# lcdTestBoard.net
KiCad netlist of a schematic drawn in EAGLE
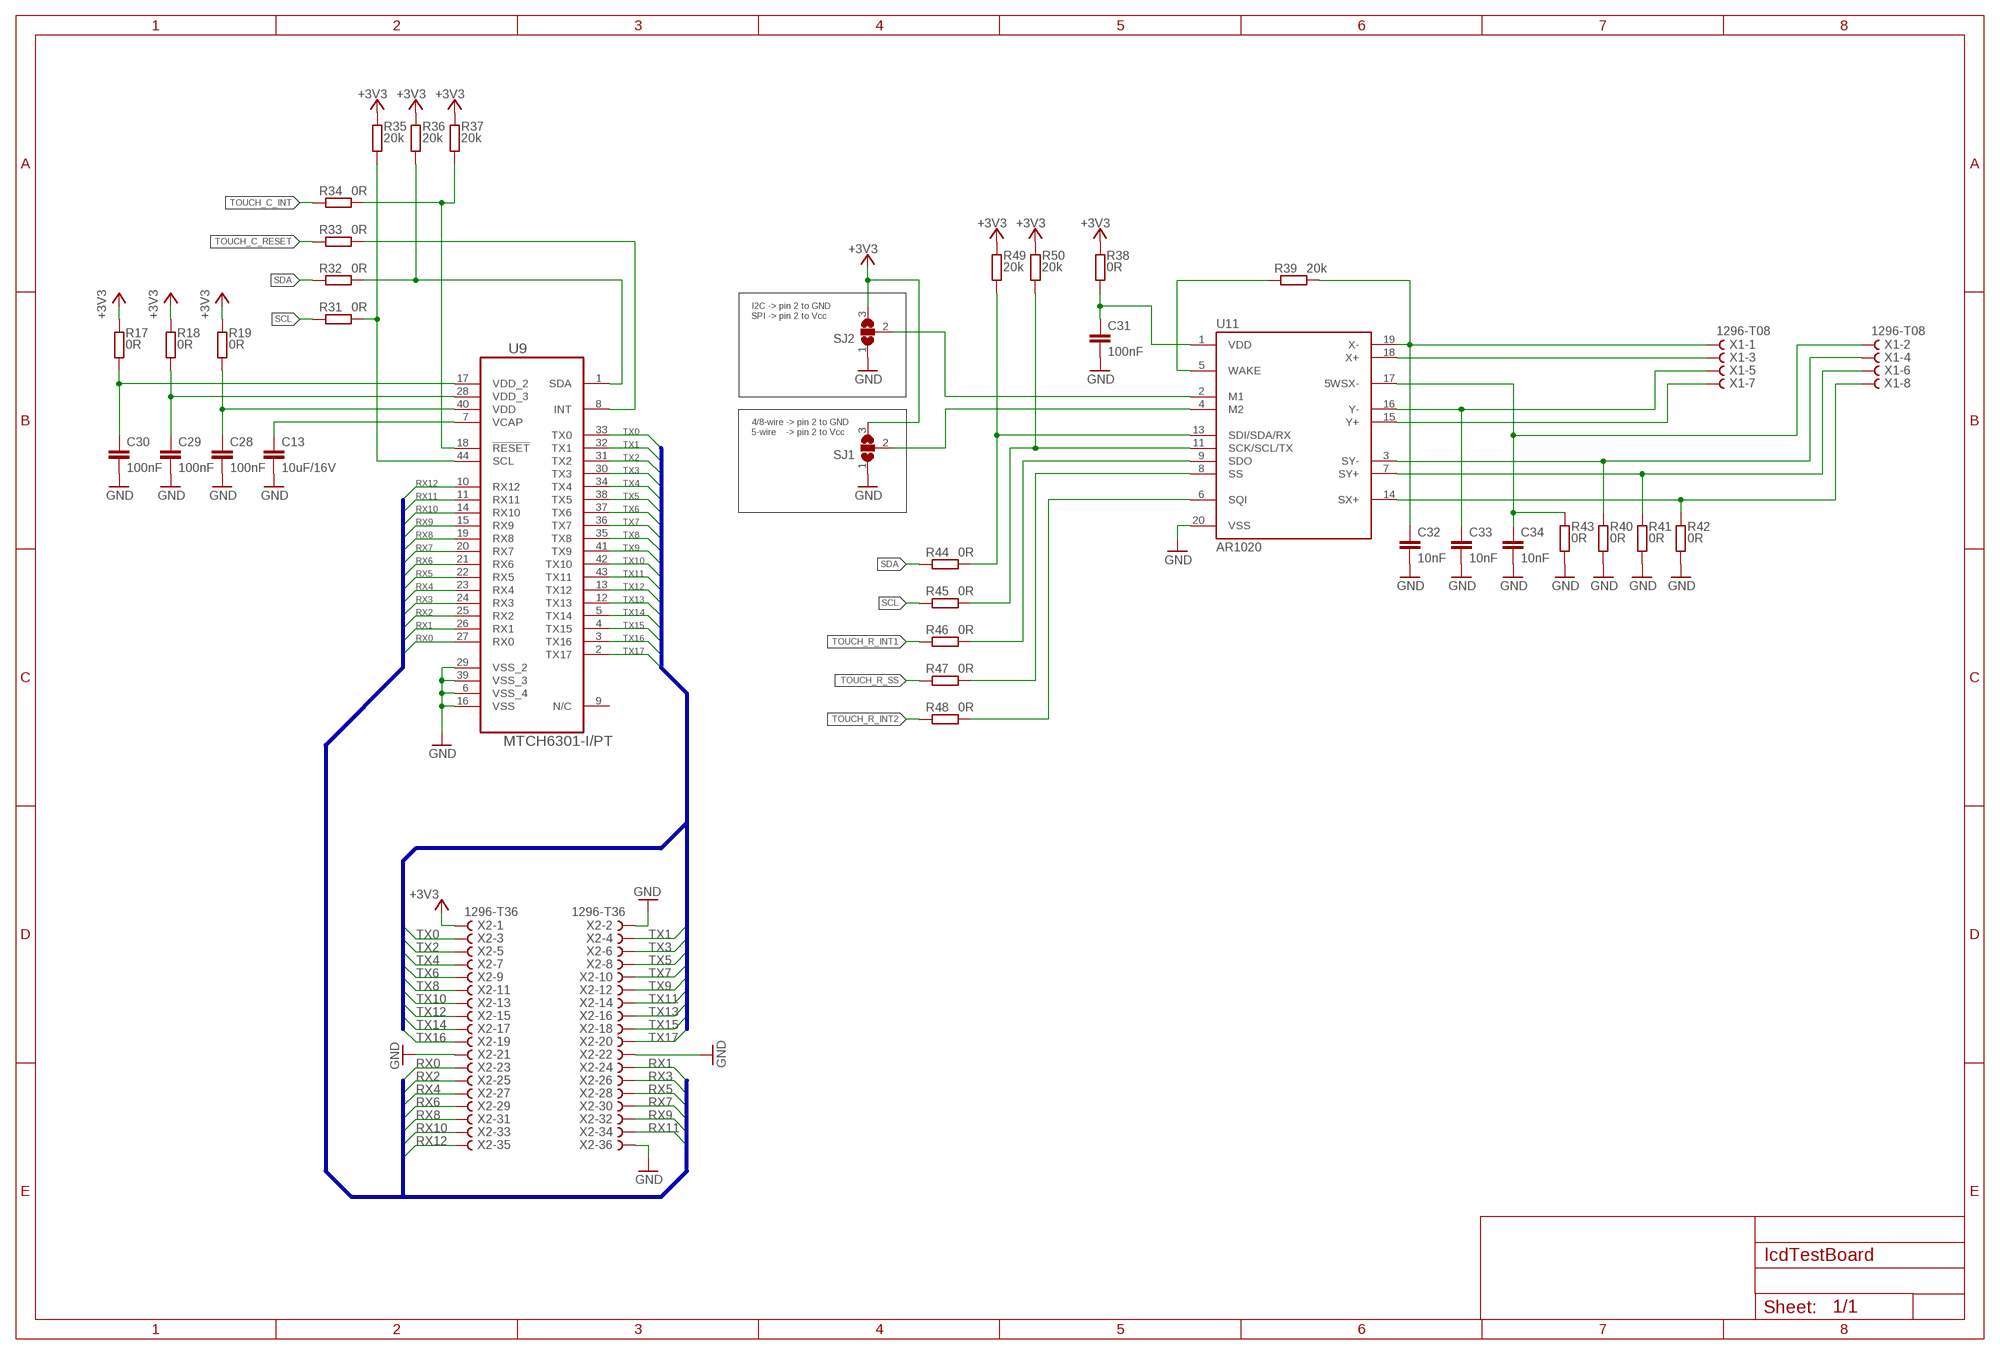
[diagram p0: schematic, sheet 1, part 1 of 3]
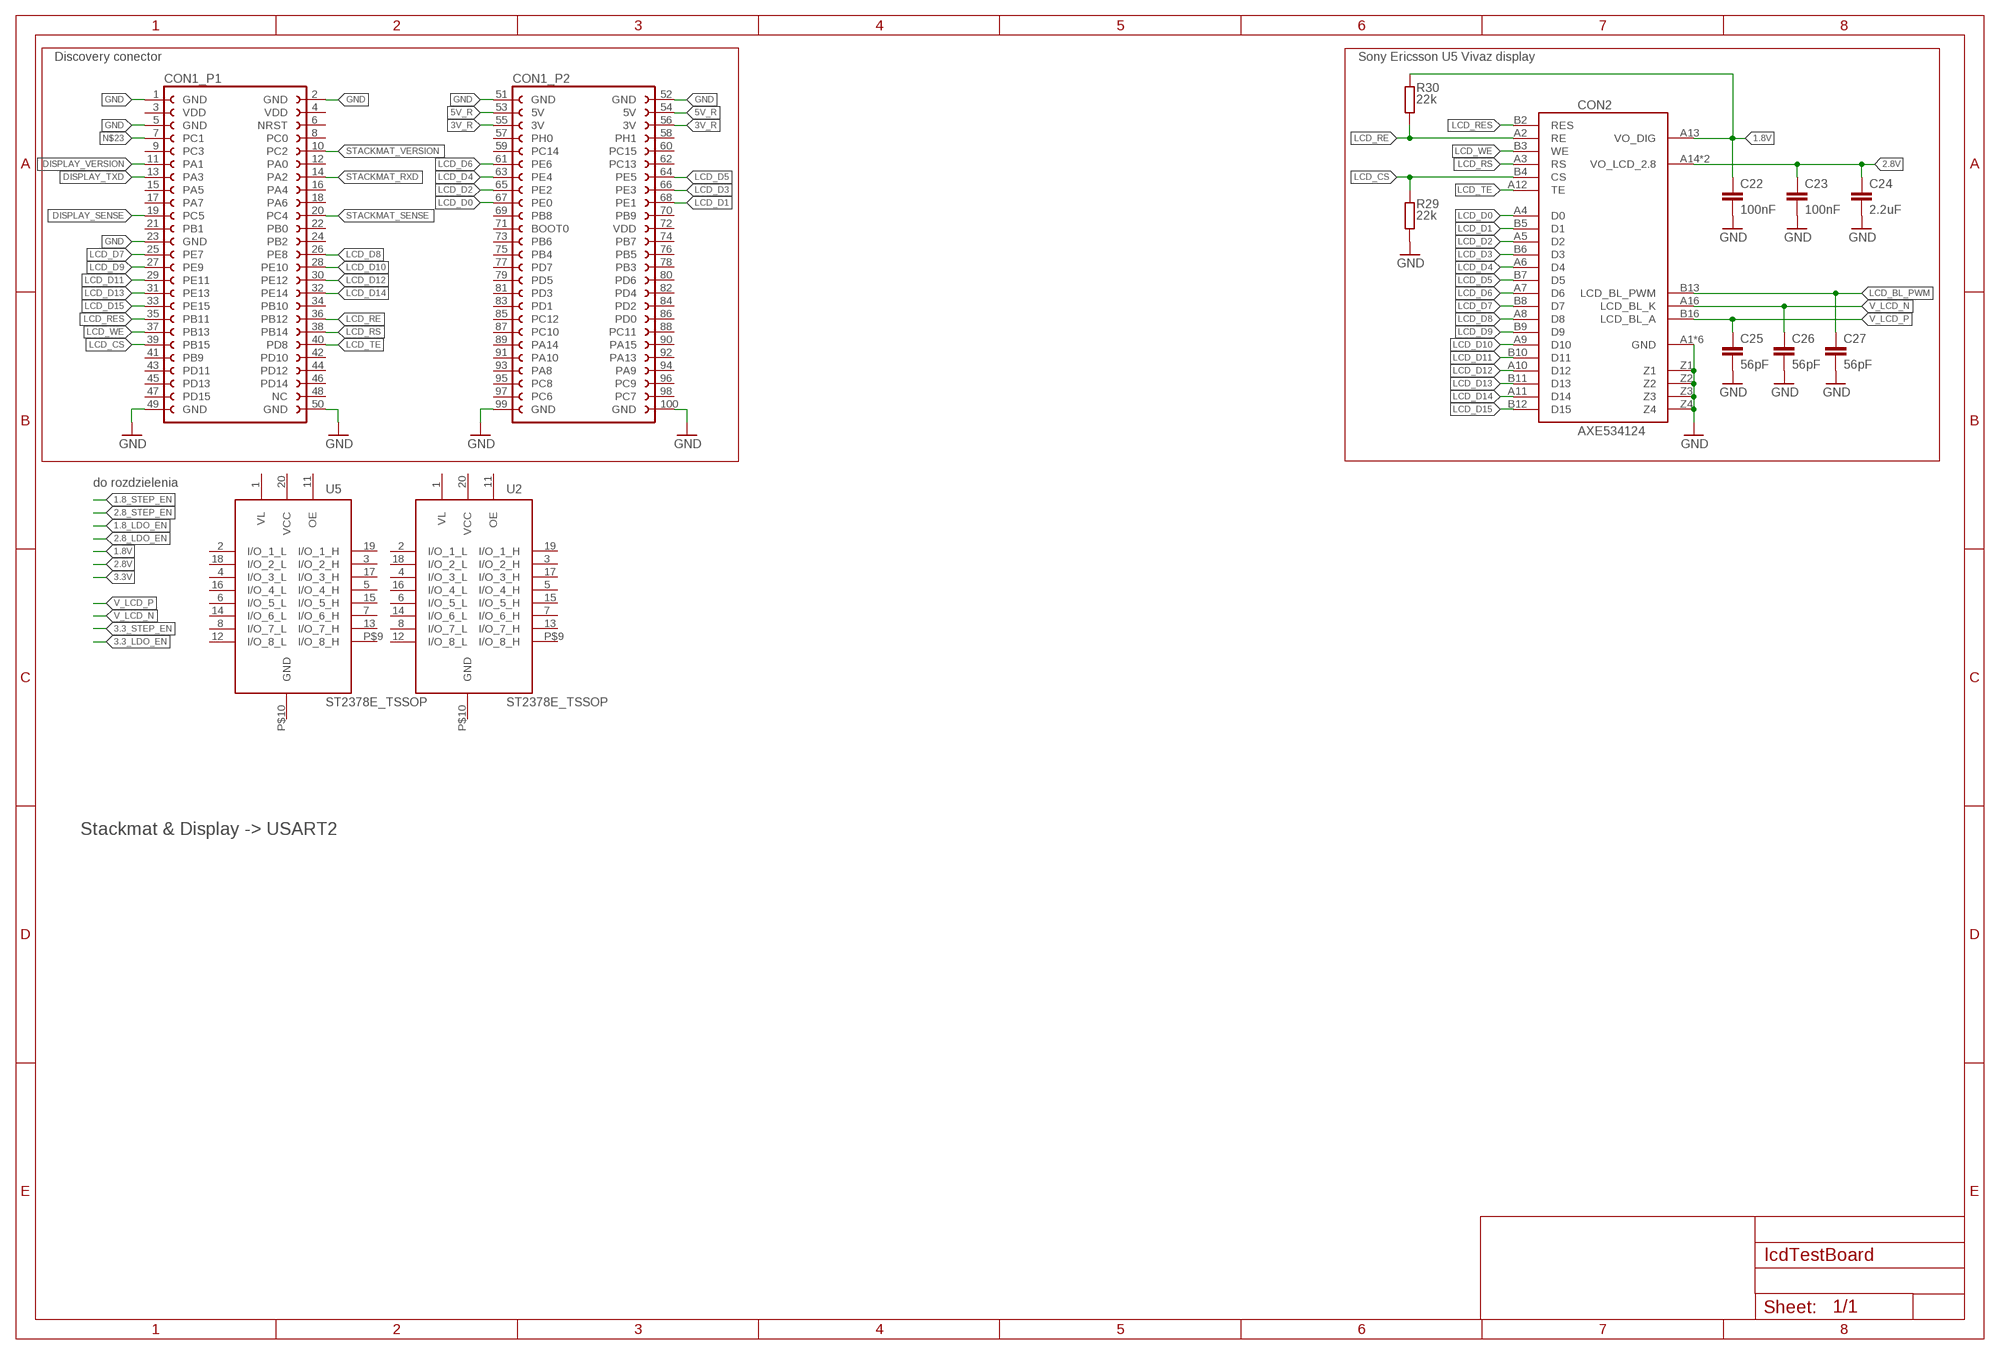
[diagram p1: schematic, sheet 1, part 2 of 3]
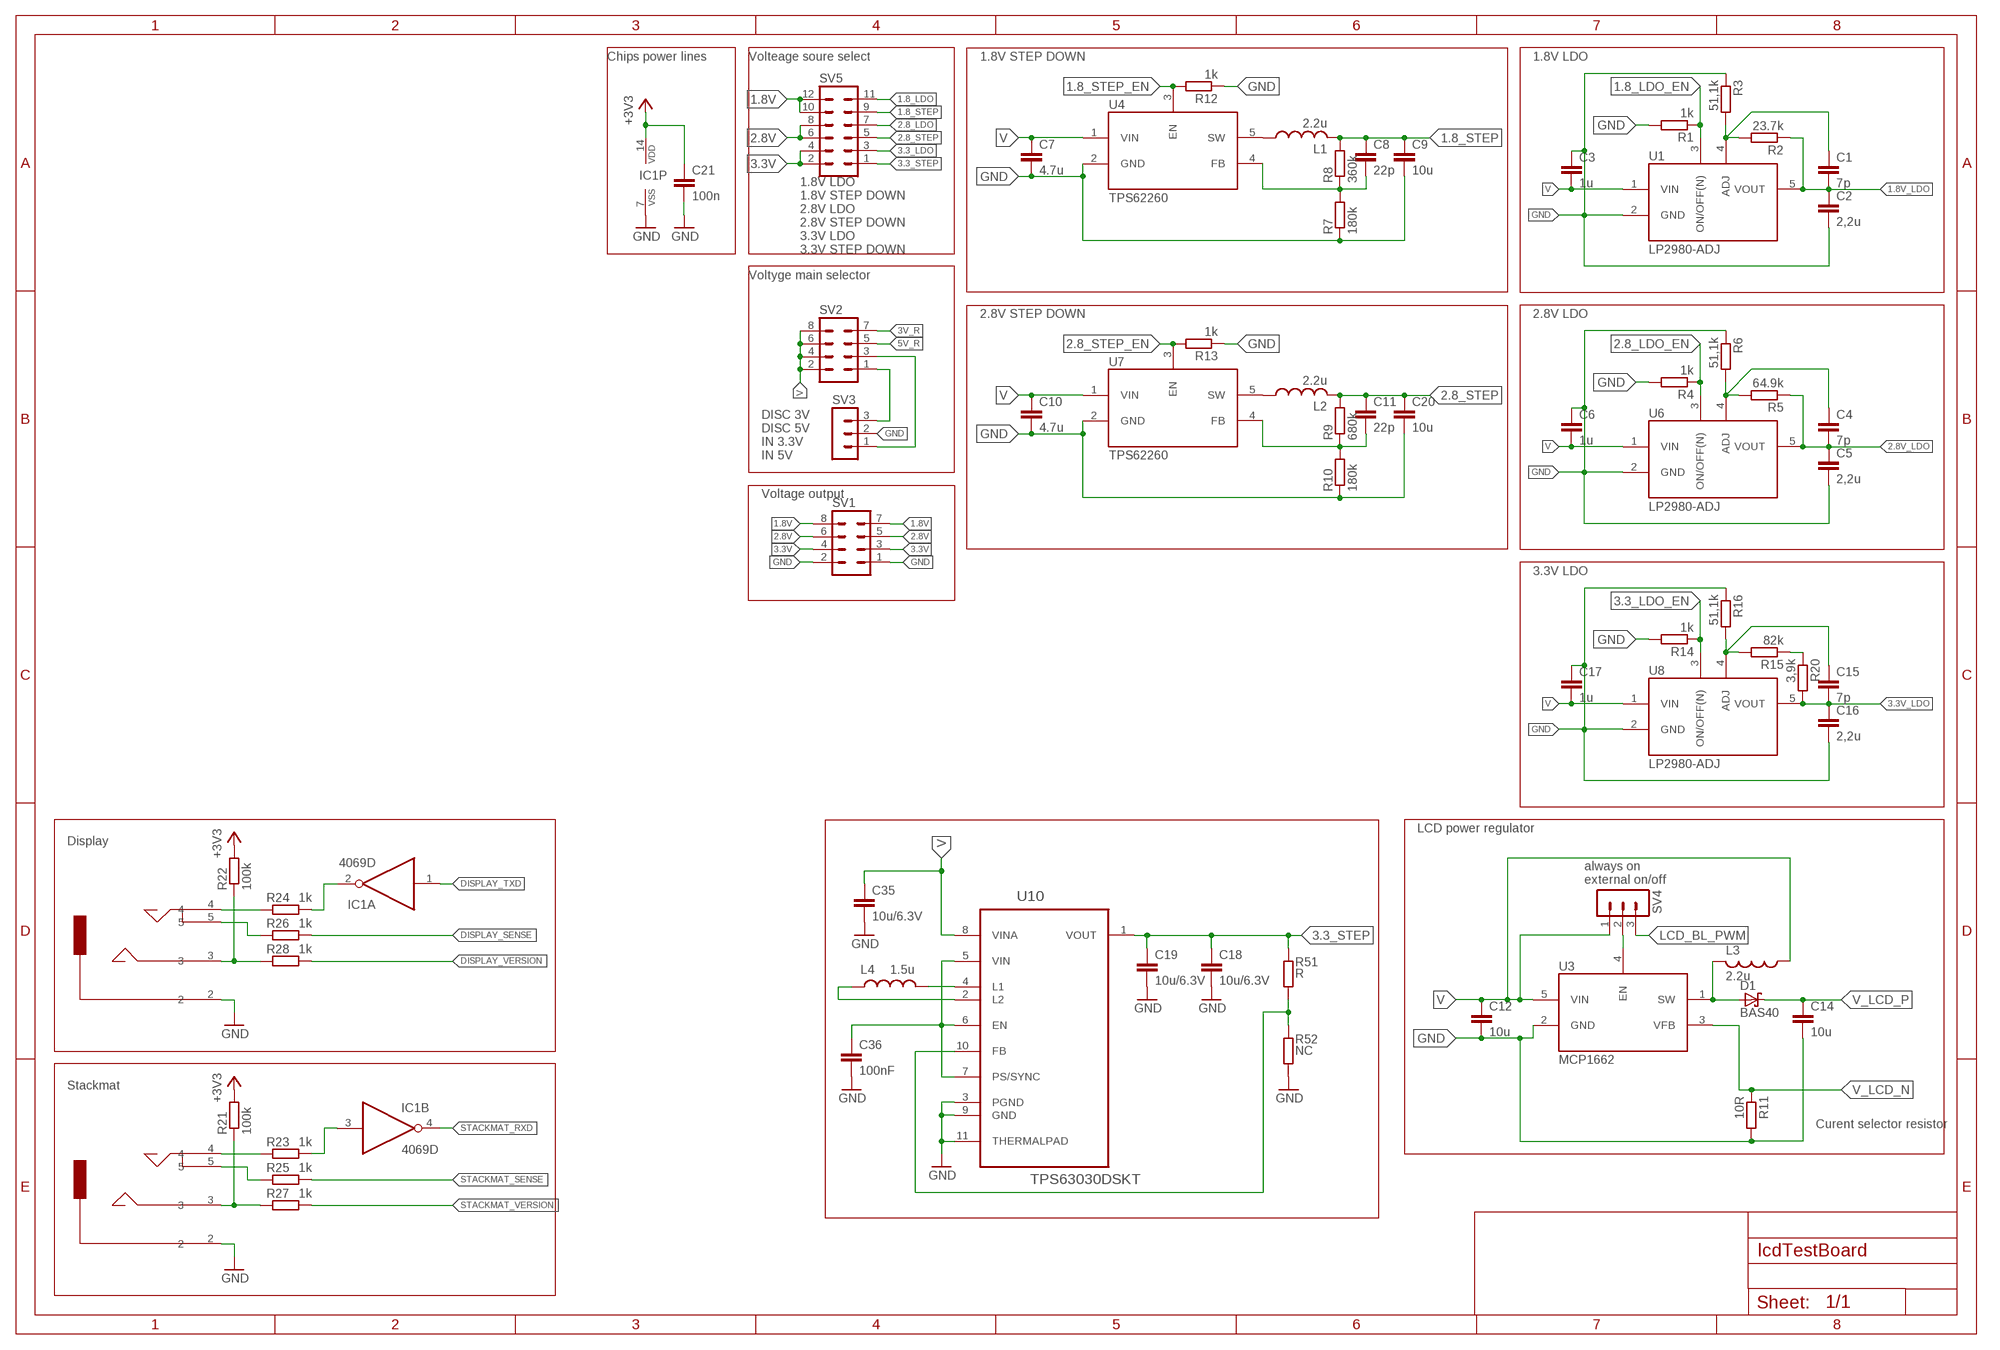
[diagram p2: schematic, sheet 1, part 3 of 3]

(export (version "E")
  (design (tool "Eeschema 10.0.6"))
  (components
    (comp (ref "C1")
      (value "7p")
      (footprint "eagle-import:C0603")
      (libsource (lib "eagle-import") (part "C-EUC0603"))
    )
    (comp (ref "C2")
      (value "2,2u")
      (footprint "eagle-import:C0603")
      (libsource (lib "eagle-import") (part "C-EUC0603"))
    )
    (comp (ref "C3")
      (value "1u")
      (footprint "eagle-import:C0603")
      (libsource (lib "eagle-import") (part "C-EUC0603"))
    )
    (comp (ref "C4")
      (value "7p")
      (footprint "eagle-import:C0603")
      (libsource (lib "eagle-import") (part "C-EUC0603"))
    )
    (comp (ref "C5")
      (value "2,2u")
      (footprint "eagle-import:C0603")
      (libsource (lib "eagle-import") (part "C-EUC0603"))
    )
    (comp (ref "C6")
      (value "1u")
      (footprint "eagle-import:C0603")
      (libsource (lib "eagle-import") (part "C-EUC0603"))
    )
    (comp (ref "C7")
      (value "4.7u")
      (footprint "eagle-import:C0603")
      (libsource (lib "eagle-import") (part "C-EUC0603"))
    )
    (comp (ref "C8")
      (value "22p")
      (footprint "eagle-import:C0603")
      (libsource (lib "eagle-import") (part "C-EUC0603"))
    )
    (comp (ref "C9")
      (value "10u")
      (footprint "eagle-import:C1206")
      (libsource (lib "eagle-import") (part "C-EUC1206"))
    )
    (comp (ref "C10")
      (value "4.7u")
      (footprint "eagle-import:C0603")
      (libsource (lib "eagle-import") (part "C-EUC0603"))
    )
    (comp (ref "C11")
      (value "22p")
      (footprint "eagle-import:C0603")
      (libsource (lib "eagle-import") (part "C-EUC0603"))
    )
    (comp (ref "C12")
      (value "10u")
      (footprint "eagle-import:C1206")
      (libsource (lib "eagle-import") (part "C-EUC1206"))
    )
    (comp (ref "C13")
      (value "10uF/16V")
      (footprint "eagle-import:C1206K")
      (libsource (lib "eagle-import") (part "C-EUC1206K"))
    )
    (comp (ref "C14")
      (value "10u")
      (footprint "eagle-import:C1206")
      (libsource (lib "eagle-import") (part "C-EUC1206"))
    )
    (comp (ref "C15")
      (value "7p")
      (footprint "eagle-import:C0603")
      (libsource (lib "eagle-import") (part "C-EUC0603"))
    )
    (comp (ref "C16")
      (value "2,2u")
      (footprint "eagle-import:C0603")
      (libsource (lib "eagle-import") (part "C-EUC0603"))
    )
    (comp (ref "C17")
      (value "1u")
      (footprint "eagle-import:C0603")
      (libsource (lib "eagle-import") (part "C-EUC0603"))
    )
    (comp (ref "C18")
      (value "10u/6.3V")
      (footprint "eagle-import:C1206")
      (libsource (lib "eagle-import") (part "C-EUC1206"))
    )
    (comp (ref "C19")
      (value "10u/6.3V")
      (footprint "eagle-import:C1206")
      (libsource (lib "eagle-import") (part "C-EUC1206"))
    )
    (comp (ref "C20")
      (value "10u")
      (footprint "eagle-import:C1206")
      (libsource (lib "eagle-import") (part "C-EUC1206"))
    )
    (comp (ref "C21")
      (value "100n")
      (footprint "eagle-import:C0603K")
      (libsource (lib "eagle-import") (part "C-EUC0603K"))
    )
    (comp (ref "C22")
      (value "100nF")
      (footprint "eagle-import:C0603K")
      (libsource (lib "eagle-import") (part "C-EUC0603K"))
    )
    (comp (ref "C23")
      (value "100nF")
      (footprint "eagle-import:C0603K")
      (libsource (lib "eagle-import") (part "C-EUC0603K"))
    )
    (comp (ref "C24")
      (value "2.2uF")
      (footprint "eagle-import:C0603K")
      (libsource (lib "eagle-import") (part "C-EUC0603K"))
    )
    (comp (ref "C25")
      (value "56pF")
      (footprint "eagle-import:C0603K")
      (libsource (lib "eagle-import") (part "C-EUC0603K"))
    )
    (comp (ref "C26")
      (value "56pF")
      (footprint "eagle-import:C0603K")
      (libsource (lib "eagle-import") (part "C-EUC0603K"))
    )
    (comp (ref "C27")
      (value "56pF")
      (footprint "eagle-import:C0603K")
      (libsource (lib "eagle-import") (part "C-EUC0603K"))
    )
    (comp (ref "C28")
      (value "100nF")
      (footprint "eagle-import:C0603K")
      (libsource (lib "eagle-import") (part "C-EUC0603K"))
    )
    (comp (ref "C29")
      (value "100nF")
      (footprint "eagle-import:C0603K")
      (libsource (lib "eagle-import") (part "C-EUC0603K"))
    )
    (comp (ref "C30")
      (value "100nF")
      (footprint "eagle-import:C0603K")
      (libsource (lib "eagle-import") (part "C-EUC0603K"))
    )
    (comp (ref "C31")
      (value "100nF")
      (footprint "eagle-import:C0603K")
      (libsource (lib "eagle-import") (part "C-EUC0603K"))
    )
    (comp (ref "C32")
      (value "10nF")
      (footprint "eagle-import:C0603K")
      (libsource (lib "eagle-import") (part "C-EUC0603K"))
    )
    (comp (ref "C33")
      (value "10nF")
      (footprint "eagle-import:C0603K")
      (libsource (lib "eagle-import") (part "C-EUC0603K"))
    )
    (comp (ref "C34")
      (value "10nF")
      (footprint "eagle-import:C0603K")
      (libsource (lib "eagle-import") (part "C-EUC0603K"))
    )
    (comp (ref "C35")
      (value "10u/6.3V")
      (footprint "eagle-import:C1206")
      (libsource (lib "eagle-import") (part "C-EUC1206"))
    )
    (comp (ref "C36")
      (value "100nF")
      (footprint "eagle-import:C1206")
      (libsource (lib "eagle-import") (part "C-EUC1206"))
    )
    (comp (ref "CON1")
      (value "STM32F4DISCOVERY-CONNECTOR")
      (footprint "eagle-import:STM32F4DISCOVERY_CONNECTOR")
      (libsource (lib "eagle-import") (part "STM32F4DISCOVERY-CONNECTOR"))
    )
    (comp (ref "CON2")
      (value "AXE534124")
      (footprint "eagle-import:SOCKET")
      (libsource (lib "eagle-import") (part "AXE534124"))
    )
    (comp (ref "D1")
      (value "BAS40")
      (footprint "eagle-import:SOT23")
      (libsource (lib "eagle-import") (part "BAS40"))
    )
    (comp (ref "IC1")
      (value "4069D")
      (footprint "eagle-import:SO14")
      (libsource (lib "eagle-import") (part "4069D"))
    )
    (comp (ref "L1")
      (value "2.2u")
      (footprint "eagle-import:L2012C")
      (libsource (lib "eagle-import") (part "L-USL2012C"))
    )
    (comp (ref "L2")
      (value "2.2u")
      (footprint "eagle-import:L2012C")
      (libsource (lib "eagle-import") (part "L-USL2012C"))
    )
    (comp (ref "L3")
      (value "2.2u")
      (footprint "eagle-import:L2012C")
      (libsource (lib "eagle-import") (part "L-USL2012C"))
    )
    (comp (ref "L4")
      (value "1.5u")
      (footprint "eagle-import:L2012C")
      (libsource (lib "eagle-import") (part "L-USL2012C"))
    )
    (comp (ref "R1")
      (value "1k")
      (footprint "eagle-import:R0603")
      (libsource (lib "eagle-import") (part "R-EU_R0603"))
    )
    (comp (ref "R2")
      (value "23.7k")
      (footprint "eagle-import:R0603")
      (libsource (lib "eagle-import") (part "R-EU_R0603"))
    )
    (comp (ref "R3")
      (value "51,1k")
      (footprint "eagle-import:R0603")
      (libsource (lib "eagle-import") (part "R-EU_R0603"))
    )
    (comp (ref "R4")
      (value "1k")
      (footprint "eagle-import:R0603")
      (libsource (lib "eagle-import") (part "R-EU_R0603"))
    )
    (comp (ref "R5")
      (value "64.9k")
      (footprint "eagle-import:R0603")
      (libsource (lib "eagle-import") (part "R-EU_R0603"))
    )
    (comp (ref "R6")
      (value "51,1k")
      (footprint "eagle-import:R0603")
      (libsource (lib "eagle-import") (part "R-EU_R0603"))
    )
    (comp (ref "R7")
      (value "180k")
      (footprint "eagle-import:R0603")
      (libsource (lib "eagle-import") (part "R-EU_R0603"))
    )
    (comp (ref "R8")
      (value "360k")
      (footprint "eagle-import:R0603")
      (libsource (lib "eagle-import") (part "R-EU_R0603"))
    )
    (comp (ref "R9")
      (value "680k")
      (footprint "eagle-import:R0603")
      (libsource (lib "eagle-import") (part "R-EU_R0603"))
    )
    (comp (ref "R10")
      (value "180k")
      (footprint "eagle-import:R0603")
      (libsource (lib "eagle-import") (part "R-EU_R0603"))
    )
    (comp (ref "R11")
      (value "10R")
      (footprint "eagle-import:R0603")
      (libsource (lib "eagle-import") (part "R-EU_R0603"))
    )
    (comp (ref "R12")
      (value "1k")
      (footprint "eagle-import:R0603")
      (libsource (lib "eagle-import") (part "R-EU_R0603"))
    )
    (comp (ref "R13")
      (value "1k")
      (footprint "eagle-import:R0603")
      (libsource (lib "eagle-import") (part "R-EU_R0603"))
    )
    (comp (ref "R14")
      (value "1k")
      (footprint "eagle-import:R0603")
      (libsource (lib "eagle-import") (part "R-EU_R0603"))
    )
    (comp (ref "R15")
      (value "82k")
      (footprint "eagle-import:R0603")
      (libsource (lib "eagle-import") (part "R-EU_R0603"))
    )
    (comp (ref "R16")
      (value "51,1k")
      (footprint "eagle-import:R0603")
      (libsource (lib "eagle-import") (part "R-EU_R0603"))
    )
    (comp (ref "R17")
      (value "0R")
      (footprint "eagle-import:R0603")
      (libsource (lib "eagle-import") (part "R-EU_R0603"))
    )
    (comp (ref "R18")
      (value "0R")
      (footprint "eagle-import:R0603")
      (libsource (lib "eagle-import") (part "R-EU_R0603"))
    )
    (comp (ref "R19")
      (value "0R")
      (footprint "eagle-import:R0603")
      (libsource (lib "eagle-import") (part "R-EU_R0603"))
    )
    (comp (ref "R20")
      (value "3,9k")
      (footprint "eagle-import:R0603")
      (libsource (lib "eagle-import") (part "R-EU_R0603"))
    )
    (comp (ref "R21")
      (value "100k")
      (footprint "eagle-import:R0603")
      (libsource (lib "eagle-import") (part "R-EU_R0603"))
    )
    (comp (ref "R22")
      (value "100k")
      (footprint "eagle-import:R0603")
      (libsource (lib "eagle-import") (part "R-EU_R0603"))
    )
    (comp (ref "R23")
      (value "1k")
      (footprint "eagle-import:R0603")
      (libsource (lib "eagle-import") (part "R-EU_R0603"))
    )
    (comp (ref "R24")
      (value "1k")
      (footprint "eagle-import:R0603")
      (libsource (lib "eagle-import") (part "R-EU_R0603"))
    )
    (comp (ref "R25")
      (value "1k")
      (footprint "eagle-import:R0603")
      (libsource (lib "eagle-import") (part "R-EU_R0603"))
    )
    (comp (ref "R26")
      (value "1k")
      (footprint "eagle-import:R0603")
      (libsource (lib "eagle-import") (part "R-EU_R0603"))
    )
    (comp (ref "R27")
      (value "1k")
      (footprint "eagle-import:R0603")
      (libsource (lib "eagle-import") (part "R-EU_R0603"))
    )
    (comp (ref "R28")
      (value "1k")
      (footprint "eagle-import:R0603")
      (libsource (lib "eagle-import") (part "R-EU_R0603"))
    )
    (comp (ref "R29")
      (value "22k")
      (footprint "eagle-import:R0603")
      (libsource (lib "eagle-import") (part "R-EU_R0603"))
    )
    (comp (ref "R30")
      (value "22k")
      (footprint "eagle-import:R0603")
      (libsource (lib "eagle-import") (part "R-EU_R0603"))
    )
    (comp (ref "R31")
      (value "0R")
      (footprint "eagle-import:R0603")
      (libsource (lib "eagle-import") (part "R-EU_R0603"))
    )
    (comp (ref "R32")
      (value "0R")
      (footprint "eagle-import:R0603")
      (libsource (lib "eagle-import") (part "R-EU_R0603"))
    )
    (comp (ref "R33")
      (value "0R")
      (footprint "eagle-import:R0603")
      (libsource (lib "eagle-import") (part "R-EU_R0603"))
    )
    (comp (ref "R34")
      (value "0R")
      (footprint "eagle-import:R0603")
      (libsource (lib "eagle-import") (part "R-EU_R0603"))
    )
    (comp (ref "R35")
      (value "20k")
      (footprint "eagle-import:R0603")
      (libsource (lib "eagle-import") (part "R-EU_R0603"))
    )
    (comp (ref "R36")
      (value "20k")
      (footprint "eagle-import:R0603")
      (libsource (lib "eagle-import") (part "R-EU_R0603"))
    )
    (comp (ref "R37")
      (value "20k")
      (footprint "eagle-import:R0603")
      (libsource (lib "eagle-import") (part "R-EU_R0603"))
    )
    (comp (ref "R38")
      (value "0R")
      (footprint "eagle-import:R0603")
      (libsource (lib "eagle-import") (part "R-EU_R0603"))
    )
    (comp (ref "R39")
      (value "20k")
      (footprint "eagle-import:R0603")
      (libsource (lib "eagle-import") (part "R-EU_R0603"))
    )
    (comp (ref "R40")
      (value "0R")
      (footprint "eagle-import:R0603")
      (libsource (lib "eagle-import") (part "R-EU_R0603"))
    )
    (comp (ref "R41")
      (value "0R")
      (footprint "eagle-import:R0603")
      (libsource (lib "eagle-import") (part "R-EU_R0603"))
    )
    (comp (ref "R42")
      (value "0R")
      (footprint "eagle-import:R0603")
      (libsource (lib "eagle-import") (part "R-EU_R0603"))
    )
    (comp (ref "R43")
      (value "0R")
      (footprint "eagle-import:R0603")
      (libsource (lib "eagle-import") (part "R-EU_R0603"))
    )
    (comp (ref "R44")
      (value "0R")
      (footprint "eagle-import:R0603")
      (libsource (lib "eagle-import") (part "R-EU_R0603"))
    )
    (comp (ref "R45")
      (value "0R")
      (footprint "eagle-import:R0603")
      (libsource (lib "eagle-import") (part "R-EU_R0603"))
    )
    (comp (ref "R46")
      (value "0R")
      (footprint "eagle-import:R0603")
      (libsource (lib "eagle-import") (part "R-EU_R0603"))
    )
    (comp (ref "R47")
      (value "0R")
      (footprint "eagle-import:R0603")
      (libsource (lib "eagle-import") (part "R-EU_R0603"))
    )
    (comp (ref "R48")
      (value "0R")
      (footprint "eagle-import:R0603")
      (libsource (lib "eagle-import") (part "R-EU_R0603"))
    )
    (comp (ref "R49")
      (value "20k")
      (footprint "eagle-import:R0603")
      (libsource (lib "eagle-import") (part "R-EU_R0603"))
    )
    (comp (ref "R50")
      (value "20k")
      (footprint "eagle-import:R0603")
      (libsource (lib "eagle-import") (part "R-EU_R0603"))
    )
    (comp (ref "R51")
      (value "R")
      (footprint "eagle-import:R0603")
      (libsource (lib "eagle-import") (part "R-EU_R0603"))
    )
    (comp (ref "R52")
      (value "NC")
      (footprint "eagle-import:R0603")
      (libsource (lib "eagle-import") (part "R-EU_R0603"))
    )
    (comp (ref "SJ1")
      (value "SJ2W")
      (footprint "eagle-import:SJ_2")
      (libsource (lib "eagle-import") (part "SJ2W"))
    )
    (comp (ref "SJ2")
      (value "SJ2W")
      (footprint "eagle-import:SJ_2")
      (libsource (lib "eagle-import") (part "SJ2W"))
    )
    (comp (ref "SV1")
      (value "MA04-2")
      (footprint "eagle-import:MA04-2")
      (libsource (lib "eagle-import") (part "MA04-2"))
    )
    (comp (ref "SV2")
      (value "MA04-2")
      (footprint "eagle-import:MA04-2")
      (libsource (lib "eagle-import") (part "MA04-2"))
    )
    (comp (ref "SV3")
      (value "MA03-1")
      (footprint "eagle-import:MA03-1")
      (libsource (lib "eagle-import") (part "MA03-1"))
    )
    (comp (ref "SV4")
      (value "MA03-1")
      (footprint "eagle-import:MA03-1")
      (libsource (lib "eagle-import") (part "MA03-1"))
    )
    (comp (ref "SV5")
      (value "MA06-2")
      (footprint "eagle-import:MA06-2")
      (libsource (lib "eagle-import") (part "MA06-2"))
    )
    (comp (ref "U$1")
      (value "PJST19GL50")
      (footprint "eagle-import:MODEL1")
      (libsource (lib "eagle-import") (part "PJST19GL50"))
    )
    (comp (ref "U$2")
      (value "PJST19GL50")
      (footprint "eagle-import:MODEL1")
      (libsource (lib "eagle-import") (part "PJST19GL50"))
    )
    (comp (ref "U1")
      (value "LP2980-ADJ")
      (footprint "eagle-import:SOT-23")
      (libsource (lib "eagle-import") (part "LP2980-ADJ"))
    )
    (comp (ref "U2")
      (value "ST2378E_TSSOP")
      (footprint "eagle-import:TSSOP20")
      (libsource (lib "eagle-import") (part "ST2378E_TSSOP"))
    )
    (comp (ref "U3")
      (value "MCP1662")
      (footprint "eagle-import:SOT-23")
      (libsource (lib "eagle-import") (part "MCP1662"))
    )
    (comp (ref "U4")
      (value "TPS62260")
      (footprint "eagle-import:SOT-23")
      (libsource (lib "eagle-import") (part "TPS62260"))
    )
    (comp (ref "U5")
      (value "ST2378E_TSSOP")
      (footprint "eagle-import:TSSOP20")
      (libsource (lib "eagle-import") (part "ST2378E_TSSOP"))
    )
    (comp (ref "U6")
      (value "LP2980-ADJ")
      (footprint "eagle-import:SOT-23")
      (libsource (lib "eagle-import") (part "LP2980-ADJ"))
    )
    (comp (ref "U7")
      (value "TPS62260")
      (footprint "eagle-import:SOT-23")
      (libsource (lib "eagle-import") (part "TPS62260"))
    )
    (comp (ref "U8")
      (value "LP2980-ADJ")
      (footprint "eagle-import:SOT-23")
      (libsource (lib "eagle-import") (part "LP2980-ADJ"))
    )
    (comp (ref "U9")
      (value "MTCH6301-I/PT")
      (footprint "eagle-import:TQFP80P1200X1200X120-44N")
      (libsource (lib "eagle-import") (part "MTCH6301-I/PT"))
    )
    (comp (ref "U10")
      (value "TPS63030DSKT")
      (footprint "eagle-import:SON50P260X260X80-11N")
      (libsource (lib "eagle-import") (part "TPS63030DSKT"))
    )
    (comp (ref "U11")
      (value "AR1020")
      (footprint "eagle-import:SSOP20")
      (libsource (lib "eagle-import") (part "AR1020"))
    )
    (comp (ref "X1")
      (value "1296-T08")
      (footprint "eagle-import:1296-08")
      (libsource (lib "eagle-import") (part "1296-T08"))
    )
    (comp (ref "X2")
      (value "1296-T36")
      (footprint "eagle-import:1296-36")
      (libsource (lib "eagle-import") (part "1296-T36"))
    )
  )
  (nets
    (net (code "1") (name "+3V3") (class "Default")
      (node (ref "C21") (pin "1") (pinfunction "1_1") (pintype "passive"))
      (node (ref "IC1") (pin "14") (pinfunction "VDD_14") (pintype "power_in"))
      (node (ref "R17") (pin "1") (pinfunction "1_1") (pintype "passive"))
      (node (ref "R18") (pin "1") (pinfunction "1_1") (pintype "passive"))
      (node (ref "R19") (pin "1") (pinfunction "1_1") (pintype "passive"))
      (node (ref "R21") (pin "2") (pinfunction "2_2") (pintype "passive"))
      (node (ref "R22") (pin "2") (pinfunction "2_2") (pintype "passive"))
      (node (ref "R35") (pin "1") (pinfunction "1_1") (pintype "passive"))
      (node (ref "R36") (pin "1") (pinfunction "1_1") (pintype "passive"))
      (node (ref "R37") (pin "1") (pinfunction "1_1") (pintype "passive"))
      (node (ref "R38") (pin "1") (pinfunction "1_1") (pintype "passive"))
      (node (ref "R49") (pin "1") (pinfunction "1_1") (pintype "passive"))
      (node (ref "R50") (pin "1") (pinfunction "1_1") (pintype "passive"))
      (node (ref "SJ1") (pin "3") (pinfunction "3_3") (pintype "passive"))
      (node (ref "SJ2") (pin "3") (pinfunction "3_3") (pintype "passive"))
      (node (ref "X2") (pin "1") (pinfunction "B_1") (pintype "passive"))
    )
    (net (code "2") (name "/RX0") (class "Default")
      (node (ref "U9") (pin "27") (pinfunction "RX0_27") (pintype "bidirectional"))
      (node (ref "X2") (pin "23") (pinfunction "B_23") (pintype "passive"))
    )
    (net (code "3") (name "/RX1") (class "Default")
      (node (ref "U9") (pin "26") (pinfunction "RX1_26") (pintype "bidirectional"))
      (node (ref "X2") (pin "24") (pinfunction "B_24") (pintype "passive"))
    )
    (net (code "4") (name "/RX2") (class "Default")
      (node (ref "U9") (pin "25") (pinfunction "RX2_25") (pintype "bidirectional"))
      (node (ref "X2") (pin "25") (pinfunction "B_25") (pintype "passive"))
    )
    (net (code "5") (name "/RX3") (class "Default")
      (node (ref "U9") (pin "24") (pinfunction "RX3_24") (pintype "bidirectional"))
      (node (ref "X2") (pin "26") (pinfunction "B_26") (pintype "passive"))
    )
    (net (code "6") (name "/RX4") (class "Default")
      (node (ref "U9") (pin "23") (pinfunction "RX4_23") (pintype "bidirectional"))
      (node (ref "X2") (pin "27") (pinfunction "B_27") (pintype "passive"))
    )
    (net (code "7") (name "/RX5") (class "Default")
      (node (ref "U9") (pin "22") (pinfunction "RX5_22") (pintype "bidirectional"))
      (node (ref "X2") (pin "28") (pinfunction "B_28") (pintype "passive"))
    )
    (net (code "8") (name "/RX6") (class "Default")
      (node (ref "U9") (pin "21") (pinfunction "RX6_21") (pintype "bidirectional"))
      (node (ref "X2") (pin "29") (pinfunction "B_29") (pintype "passive"))
    )
    (net (code "9") (name "/RX7") (class "Default")
      (node (ref "U9") (pin "20") (pinfunction "RX7_20") (pintype "bidirectional"))
      (node (ref "X2") (pin "30") (pinfunction "B_30") (pintype "passive"))
    )
    (net (code "10") (name "/RX8") (class "Default")
      (node (ref "U9") (pin "19") (pinfunction "RX8_19") (pintype "bidirectional"))
      (node (ref "X2") (pin "31") (pinfunction "B_31") (pintype "passive"))
    )
    (net (code "11") (name "/RX9") (class "Default")
      (node (ref "U9") (pin "15") (pinfunction "RX9_15") (pintype "bidirectional"))
      (node (ref "X2") (pin "32") (pinfunction "B_32") (pintype "passive"))
    )
    (net (code "12") (name "/RX10") (class "Default")
      (node (ref "U9") (pin "14") (pinfunction "RX10_14") (pintype "bidirectional"))
      (node (ref "X2") (pin "33") (pinfunction "B_33") (pintype "passive"))
    )
    (net (code "13") (name "/RX11") (class "Default")
      (node (ref "U9") (pin "11") (pinfunction "RX11_11") (pintype "bidirectional"))
      (node (ref "X2") (pin "34") (pinfunction "B_34") (pintype "passive"))
    )
    (net (code "14") (name "/RX12") (class "Default")
      (node (ref "U9") (pin "10") (pinfunction "RX12_10") (pintype "bidirectional"))
      (node (ref "X2") (pin "35") (pinfunction "B_35") (pintype "passive"))
    )
    (net (code "15") (name "/TX0") (class "Default")
      (node (ref "U9") (pin "33") (pinfunction "TX0_33") (pintype "output"))
      (node (ref "X2") (pin "3") (pinfunction "B_3") (pintype "passive"))
    )
    (net (code "16") (name "/TX1") (class "Default")
      (node (ref "U9") (pin "32") (pinfunction "TX1_32") (pintype "output"))
      (node (ref "X2") (pin "4") (pinfunction "B_4") (pintype "passive"))
    )
    (net (code "17") (name "/TX2") (class "Default")
      (node (ref "U9") (pin "31") (pinfunction "TX2_31") (pintype "output"))
      (node (ref "X2") (pin "5") (pinfunction "B_5") (pintype "passive"))
    )
    (net (code "18") (name "/TX3") (class "Default")
      (node (ref "U9") (pin "30") (pinfunction "TX3_30") (pintype "output"))
      (node (ref "X2") (pin "6") (pinfunction "B_6") (pintype "passive"))
    )
    (net (code "19") (name "/TX4") (class "Default")
      (node (ref "U9") (pin "34") (pinfunction "TX4_34") (pintype "output"))
      (node (ref "X2") (pin "7") (pinfunction "B_7") (pintype "passive"))
    )
    (net (code "20") (name "/TX5") (class "Default")
      (node (ref "U9") (pin "38") (pinfunction "TX5_38") (pintype "output"))
      (node (ref "X2") (pin "8") (pinfunction "B_8") (pintype "passive"))
    )
    (net (code "21") (name "/TX6") (class "Default")
      (node (ref "U9") (pin "37") (pinfunction "TX6_37") (pintype "output"))
      (node (ref "X2") (pin "9") (pinfunction "B_9") (pintype "passive"))
    )
    (net (code "22") (name "/TX7") (class "Default")
      (node (ref "U9") (pin "36") (pinfunction "TX7_36") (pintype "output"))
      (node (ref "X2") (pin "10") (pinfunction "B_10") (pintype "passive"))
    )
    (net (code "23") (name "/TX8") (class "Default")
      (node (ref "U9") (pin "35") (pinfunction "TX8_35") (pintype "output"))
      (node (ref "X2") (pin "11") (pinfunction "B_11") (pintype "passive"))
    )
    (net (code "24") (name "/TX9") (class "Default")
      (node (ref "U9") (pin "41") (pinfunction "TX9_41") (pintype "output"))
      (node (ref "X2") (pin "12") (pinfunction "B_12") (pintype "passive"))
    )
    (net (code "25") (name "/TX10") (class "Default")
      (node (ref "U9") (pin "42") (pinfunction "TX10_42") (pintype "output"))
      (node (ref "X2") (pin "13") (pinfunction "B_13") (pintype "passive"))
    )
    (net (code "26") (name "/TX11") (class "Default")
      (node (ref "U9") (pin "43") (pinfunction "TX11_43") (pintype "output"))
      (node (ref "X2") (pin "14") (pinfunction "B_14") (pintype "passive"))
    )
    (net (code "27") (name "/TX12") (class "Default")
      (node (ref "U9") (pin "13") (pinfunction "TX12_13") (pintype "output"))
      (node (ref "X2") (pin "15") (pinfunction "B_15") (pintype "passive"))
    )
    (net (code "28") (name "/TX13") (class "Default")
      (node (ref "U9") (pin "12") (pinfunction "TX13_12") (pintype "output"))
      (node (ref "X2") (pin "16") (pinfunction "B_16") (pintype "passive"))
    )
    (net (code "29") (name "/TX14") (class "Default")
      (node (ref "U9") (pin "5") (pinfunction "TX14_5") (pintype "output"))
      (node (ref "X2") (pin "17") (pinfunction "B_17") (pintype "passive"))
    )
    (net (code "30") (name "/TX15") (class "Default")
      (node (ref "U9") (pin "4") (pinfunction "TX15_4") (pintype "output"))
      (node (ref "X2") (pin "18") (pinfunction "B_18") (pintype "passive"))
    )
    (net (code "31") (name "/TX16") (class "Default")
      (node (ref "U9") (pin "3") (pinfunction "TX16_3") (pintype "output"))
      (node (ref "X2") (pin "19") (pinfunction "B_19") (pintype "passive"))
    )
    (net (code "32") (name "/TX17") (class "Default")
      (node (ref "U9") (pin "2") (pinfunction "TX17_2") (pintype "output"))
      (node (ref "X2") (pin "20") (pinfunction "B_20") (pintype "passive"))
    )
    (net (code "33") (name "1.8V") (class "Default")
      (node (ref "C22") (pin "1") (pinfunction "1_1") (pintype "passive"))
      (node (ref "CON2") (pin "A13") (pinfunction "VO_DIG_A13") (pintype "bidirectional"))
      (node (ref "R30") (pin "1") (pinfunction "1_1") (pintype "passive"))
      (node (ref "SV1") (pin "7") (pinfunction "7_7") (pintype "passive"))
      (node (ref "SV1") (pin "8") (pinfunction "8_8") (pintype "passive"))
      (node (ref "SV5") (pin "10") (pinfunction "10_10") (pintype "passive"))
      (node (ref "SV5") (pin "12") (pinfunction "12_12") (pintype "passive"))
    )
    (net (code "34") (name "1.8V_LDO") (class "Default")
      (node (ref "C1") (pin "2") (pinfunction "2_2") (pintype "passive"))
      (node (ref "C2") (pin "1") (pinfunction "1_1") (pintype "passive"))
      (node (ref "R2") (pin "1") (pinfunction "1_1") (pintype "passive"))
      (node (ref "U1") (pin "5") (pinfunction "VOUT_5") (pintype "bidirectional"))
    )
    (net (code "35") (name "1.8_LDO") (class "Default")
      (node (ref "SV5") (pin "11") (pinfunction "11_11") (pintype "passive"))
    )
    (net (code "36") (name "1.8_LDO_EN") (class "Default")
      (node (ref "R1") (pin "1") (pinfunction "1_1") (pintype "passive"))
      (node (ref "U1") (pin "3") (pinfunction "ON/OFF(N)_3") (pintype "bidirectional"))
    )
    (net (code "37") (name "1.8_STEP") (class "Default")
      (node (ref "C8") (pin "1") (pinfunction "1_1") (pintype "passive"))
      (node (ref "C9") (pin "1") (pinfunction "1_1") (pintype "passive"))
      (node (ref "L1") (pin "2") (pinfunction "2_2") (pintype "passive"))
      (node (ref "R8") (pin "2") (pinfunction "2_2") (pintype "passive"))
      (node (ref "SV5") (pin "9") (pinfunction "9_9") (pintype "passive"))
    )
    (net (code "38") (name "1.8_STEP_EN") (class "Default")
      (node (ref "R12") (pin "2") (pinfunction "2_2") (pintype "passive"))
      (node (ref "U4") (pin "3") (pinfunction "EN_3") (pintype "bidirectional"))
    )
    (net (code "39") (name "2.8V") (class "Default")
      (node (ref "C23") (pin "1") (pinfunction "1_1") (pintype "passive"))
      (node (ref "C24") (pin "1") (pinfunction "1_1") (pintype "passive"))
      (node (ref "CON2") (pin "A14") (pinfunction "VO_LCD_2.8_A14") (pintype "bidirectional"))
      (node (ref "CON2") (pin "B14") (pinfunction "VO_LCD_2.8_B14") (pintype "bidirectional"))
      (node (ref "SV1") (pin "5") (pinfunction "5_5") (pintype "passive"))
      (node (ref "SV1") (pin "6") (pinfunction "6_6") (pintype "passive"))
      (node (ref "SV5") (pin "6") (pinfunction "6_6") (pintype "passive"))
      (node (ref "SV5") (pin "8") (pinfunction "8_8") (pintype "passive"))
    )
    (net (code "40") (name "2.8V_LDO") (class "Default")
      (node (ref "C4") (pin "2") (pinfunction "2_2") (pintype "passive"))
      (node (ref "C5") (pin "1") (pinfunction "1_1") (pintype "passive"))
      (node (ref "R5") (pin "1") (pinfunction "1_1") (pintype "passive"))
      (node (ref "U6") (pin "5") (pinfunction "VOUT_5") (pintype "bidirectional"))
    )
    (net (code "41") (name "2.8_LDO") (class "Default")
      (node (ref "SV5") (pin "7") (pinfunction "7_7") (pintype "passive"))
    )
    (net (code "42") (name "2.8_LDO_EN") (class "Default")
      (node (ref "R4") (pin "1") (pinfunction "1_1") (pintype "passive"))
      (node (ref "U6") (pin "3") (pinfunction "ON/OFF(N)_3") (pintype "bidirectional"))
    )
    (net (code "43") (name "2.8_STEP") (class "Default")
      (node (ref "C11") (pin "1") (pinfunction "1_1") (pintype "passive"))
      (node (ref "C20") (pin "1") (pinfunction "1_1") (pintype "passive"))
      (node (ref "L2") (pin "2") (pinfunction "2_2") (pintype "passive"))
      (node (ref "R9") (pin "2") (pinfunction "2_2") (pintype "passive"))
      (node (ref "SV5") (pin "5") (pinfunction "5_5") (pintype "passive"))
    )
    (net (code "44") (name "2.8_STEP_EN") (class "Default")
      (node (ref "R13") (pin "2") (pinfunction "2_2") (pintype "passive"))
      (node (ref "U7") (pin "3") (pinfunction "EN_3") (pintype "bidirectional"))
    )
    (net (code "45") (name "3.3V") (class "Default")
      (node (ref "SV1") (pin "3") (pinfunction "3_3") (pintype "passive"))
      (node (ref "SV1") (pin "4") (pinfunction "4_4") (pintype "passive"))
      (node (ref "SV5") (pin "2") (pinfunction "2_2") (pintype "passive"))
      (node (ref "SV5") (pin "4") (pinfunction "4_4") (pintype "passive"))
    )
    (net (code "46") (name "3.3V_LDO") (class "Default")
      (node (ref "C15") (pin "2") (pinfunction "2_2") (pintype "passive"))
      (node (ref "C16") (pin "1") (pinfunction "1_1") (pintype "passive"))
      (node (ref "R20") (pin "2") (pinfunction "2_2") (pintype "passive"))
      (node (ref "U8") (pin "5") (pinfunction "VOUT_5") (pintype "bidirectional"))
    )
    (net (code "47") (name "3.3_LDO") (class "Default")
      (node (ref "SV5") (pin "3") (pinfunction "3_3") (pintype "passive"))
    )
    (net (code "48") (name "3.3_LDO_EN") (class "Default")
      (node (ref "R14") (pin "1") (pinfunction "1_1") (pintype "passive"))
      (node (ref "U8") (pin "3") (pinfunction "ON/OFF(N)_3") (pintype "bidirectional"))
    )
    (net (code "49") (name "3.3_STEP") (class "Default")
      (node (ref "C18") (pin "1") (pinfunction "1_1") (pintype "passive"))
      (node (ref "C19") (pin "1") (pinfunction "1_1") (pintype "passive"))
      (node (ref "R51") (pin "1") (pinfunction "1_1") (pintype "passive"))
      (node (ref "SV5") (pin "1") (pinfunction "1_1") (pintype "passive"))
      (node (ref "U10") (pin "1") (pinfunction "VOUT_1") (pintype "power_in"))
    )
    (net (code "51") (name "3V_R") (class "Default")
      (node (ref "CON1") (pin "55") (pinfunction "3V_55") (pintype "passive"))
      (node (ref "CON1") (pin "56") (pinfunction "3V_56") (pintype "passive"))
      (node (ref "SV2") (pin "7") (pinfunction "7_7") (pintype "passive"))
    )
    (net (code "52") (name "5V_R") (class "Default")
      (node (ref "CON1") (pin "53") (pinfunction "5V_53") (pintype "passive"))
      (node (ref "CON1") (pin "54") (pinfunction "5V_54") (pintype "passive"))
      (node (ref "SV2") (pin "5") (pinfunction "5_5") (pintype "passive"))
    )
    (net (code "53") (name "DISPLAY_SENSE") (class "Default")
      (node (ref "CON1") (pin "19") (pinfunction "PC5_19") (pintype "passive"))
      (node (ref "R26") (pin "1") (pinfunction "1_1") (pintype "passive"))
    )
    (net (code "54") (name "DISPLAY_TXD") (class "Default")
      (node (ref "CON1") (pin "13") (pinfunction "PA3_13") (pintype "passive"))
      (node (ref "IC1") (pin "1") (pinfunction "I_1") (pintype "input"))
    )
    (net (code "55") (name "DISPLAY_VERSION") (class "Default")
      (node (ref "CON1") (pin "11") (pinfunction "PA1_11") (pintype "passive"))
      (node (ref "R28") (pin "1") (pinfunction "1_1") (pintype "passive"))
    )
    (net (code "56") (name "GND") (class "Default")
      (node (ref "C10") (pin "2") (pinfunction "2_2") (pintype "passive"))
      (node (ref "C12") (pin "2") (pinfunction "2_2") (pintype "passive"))
      (node (ref "C13") (pin "2") (pinfunction "2_2") (pintype "passive"))
      (node (ref "C14") (pin "2") (pinfunction "2_2") (pintype "passive"))
      (node (ref "C16") (pin "2") (pinfunction "2_2") (pintype "passive"))
      (node (ref "C17") (pin "1") (pinfunction "1_1") (pintype "passive"))
      (node (ref "C18") (pin "2") (pinfunction "2_2") (pintype "passive"))
      (node (ref "C19") (pin "2") (pinfunction "2_2") (pintype "passive"))
      (node (ref "C2") (pin "2") (pinfunction "2_2") (pintype "passive"))
      (node (ref "C20") (pin "2") (pinfunction "2_2") (pintype "passive"))
      (node (ref "C21") (pin "2") (pinfunction "2_2") (pintype "passive"))
      (node (ref "C22") (pin "2") (pinfunction "2_2") (pintype "passive"))
      (node (ref "C23") (pin "2") (pinfunction "2_2") (pintype "passive"))
      (node (ref "C24") (pin "2") (pinfunction "2_2") (pintype "passive"))
      (node (ref "C25") (pin "2") (pinfunction "2_2") (pintype "passive"))
      (node (ref "C26") (pin "2") (pinfunction "2_2") (pintype "passive"))
      (node (ref "C27") (pin "2") (pinfunction "2_2") (pintype "passive"))
      (node (ref "C28") (pin "2") (pinfunction "2_2") (pintype "passive"))
      (node (ref "C29") (pin "2") (pinfunction "2_2") (pintype "passive"))
      (node (ref "C3") (pin "1") (pinfunction "1_1") (pintype "passive"))
      (node (ref "C30") (pin "2") (pinfunction "2_2") (pintype "passive"))
      (node (ref "C31") (pin "2") (pinfunction "2_2") (pintype "passive"))
      (node (ref "C32") (pin "2") (pinfunction "2_2") (pintype "passive"))
      (node (ref "C33") (pin "2") (pinfunction "2_2") (pintype "passive"))
      (node (ref "C34") (pin "2") (pinfunction "2_2") (pintype "passive"))
      (node (ref "C35") (pin "2") (pinfunction "2_2") (pintype "passive"))
      (node (ref "C36") (pin "2") (pinfunction "2_2") (pintype "passive"))
      (node (ref "C5") (pin "2") (pinfunction "2_2") (pintype "passive"))
      (node (ref "C6") (pin "1") (pinfunction "1_1") (pintype "passive"))
      (node (ref "C7") (pin "2") (pinfunction "2_2") (pintype "passive"))
      (node (ref "C9") (pin "2") (pinfunction "2_2") (pintype "passive"))
      (node (ref "CON1") (pin "1") (pinfunction "GND_1") (pintype "passive"))
      (node (ref "CON1") (pin "100") (pinfunction "GND_100") (pintype "passive"))
      (node (ref "CON1") (pin "2") (pinfunction "GND_2") (pintype "passive"))
      (node (ref "CON1") (pin "23") (pinfunction "GND_23") (pintype "passive"))
      (node (ref "CON1") (pin "49") (pinfunction "GND_49") (pintype "passive"))
      (node (ref "CON1") (pin "5") (pinfunction "GND_5") (pintype "passive"))
      (node (ref "CON1") (pin "50") (pinfunction "GND_50") (pintype "passive"))
      (node (ref "CON1") (pin "51") (pinfunction "GND_51") (pintype "passive"))
      (node (ref "CON1") (pin "52") (pinfunction "GND_52") (pintype "passive"))
      (node (ref "CON1") (pin "99") (pinfunction "GND_99") (pintype "passive"))
      (node (ref "CON2") (pin "A1") (pinfunction "GND_A1") (pintype "bidirectional"))
      (node (ref "CON2") (pin "A15") (pinfunction "GND_A15") (pintype "bidirectional"))
      (node (ref "CON2") (pin "A17") (pinfunction "GND_A17") (pintype "bidirectional"))
      (node (ref "CON2") (pin "B1") (pinfunction "GND_B1") (pintype "bidirectional"))
      (node (ref "CON2") (pin "B15") (pinfunction "GND_B15") (pintype "bidirectional"))
      (node (ref "CON2") (pin "B17") (pinfunction "GND_B17") (pintype "bidirectional"))
      (node (ref "CON2") (pin "Z1") (pinfunction "Z1_Z1") (pintype "bidirectional"))
      (node (ref "CON2") (pin "Z2") (pinfunction "Z2_Z2") (pintype "bidirectional"))
      (node (ref "CON2") (pin "Z3") (pinfunction "Z3_Z3") (pintype "bidirectional"))
      (node (ref "CON2") (pin "Z4") (pinfunction "Z4_Z4") (pintype "bidirectional"))
      (node (ref "IC1") (pin "7") (pinfunction "VSS_7") (pintype "power_in"))
      (node (ref "R1") (pin "2") (pinfunction "2_2") (pintype "passive"))
      (node (ref "R10") (pin "1") (pinfunction "1_1") (pintype "passive"))
      (node (ref "R11") (pin "2") (pinfunction "2_2") (pintype "passive"))
      (node (ref "R12") (pin "1") (pinfunction "1_1") (pintype "passive"))
      (node (ref "R13") (pin "1") (pinfunction "1_1") (pintype "passive"))
      (node (ref "R14") (pin "2") (pinfunction "2_2") (pintype "passive"))
      (node (ref "R16") (pin "1") (pinfunction "1_1") (pintype "passive"))
      (node (ref "R29") (pin "2") (pinfunction "2_2") (pintype "passive"))
      (node (ref "R3") (pin "1") (pinfunction "1_1") (pintype "passive"))
      (node (ref "R4") (pin "2") (pinfunction "2_2") (pintype "passive"))
      (node (ref "R40") (pin "2") (pinfunction "2_2") (pintype "passive"))
      (node (ref "R41") (pin "2") (pinfunction "2_2") (pintype "passive"))
      (node (ref "R42") (pin "2") (pinfunction "2_2") (pintype "passive"))
      (node (ref "R43") (pin "2") (pinfunction "2_2") (pintype "passive"))
      (node (ref "R52") (pin "2") (pinfunction "2_2") (pintype "passive"))
      (node (ref "R6") (pin "1") (pinfunction "1_1") (pintype "passive"))
      (node (ref "R7") (pin "1") (pinfunction "1_1") (pintype "passive"))
      (node (ref "SJ1") (pin "1") (pinfunction "1_1") (pintype "passive"))
      (node (ref "SJ2") (pin "1") (pinfunction "1_1") (pintype "passive"))
      (node (ref "SV1") (pin "1") (pinfunction "1_1") (pintype "passive"))
      (node (ref "SV1") (pin "2") (pinfunction "2_2") (pintype "passive"))
      (node (ref "SV2") (pin "1") (pinfunction "1_1") (pintype "passive"))
      (node (ref "SV3") (pin "3") (pinfunction "3_3") (pintype "passive"))
      (node (ref "U$1") (pin "2") (pinfunction "2_2") (pintype "bidirectional"))
      (node (ref "U$2") (pin "2") (pinfunction "2_2") (pintype "bidirectional"))
      (node (ref "U1") (pin "2") (pinfunction "GND_2") (pintype "bidirectional"))
      (node (ref "U10") (pin "11") (pinfunction "THERMALPAD_11") (pintype "passive"))
      (node (ref "U10") (pin "3") (pinfunction "PGND_3") (pintype "power_in"))
      (node (ref "U10") (pin "9") (pinfunction "GND_9") (pintype "power_in"))
      (node (ref "U11") (pin "20") (pinfunction "VSS_20") (pintype "bidirectional"))
      (node (ref "U3") (pin "2") (pinfunction "GND_2") (pintype "bidirectional"))
      (node (ref "U4") (pin "2") (pinfunction "GND_2") (pintype "bidirectional"))
      (node (ref "U6") (pin "2") (pinfunction "GND_2") (pintype "bidirectional"))
      (node (ref "U7") (pin "2") (pinfunction "GND_2") (pintype "bidirectional"))
      (node (ref "U8") (pin "2") (pinfunction "GND_2") (pintype "bidirectional"))
      (node (ref "U9") (pin "16") (pinfunction "VSS_16") (pintype "power_in"))
      (node (ref "U9") (pin "29") (pinfunction "VSS_2_29") (pintype "power_in"))
      (node (ref "U9") (pin "39") (pinfunction "VSS_3_39") (pintype "power_in"))
      (node (ref "U9") (pin "6") (pinfunction "VSS_4_6") (pintype "power_in"))
      (node (ref "X2") (pin "2") (pinfunction "B_2") (pintype "passive"))
      (node (ref "X2") (pin "21") (pinfunction "B_21") (pintype "passive"))
      (node (ref "X2") (pin "22") (pinfunction "B_22") (pintype "passive"))
      (node (ref "X2") (pin "36") (pinfunction "B_36") (pintype "passive"))
    )
    (net (code "57") (name "LCD_BL_PWM") (class "Default")
      (node (ref "C27") (pin "1") (pinfunction "1_1") (pintype "passive"))
      (node (ref "CON2") (pin "B13") (pinfunction "LCD_BL_PWM_B13") (pintype "output"))
      (node (ref "SV4") (pin "3") (pinfunction "3_3") (pintype "passive"))
    )
    (net (code "58") (name "LCD_CS") (class "Default")
      (node (ref "CON1") (pin "39") (pinfunction "PB15_39") (pintype "passive"))
      (node (ref "CON2") (pin "B4") (pinfunction "CS_B4") (pintype "bidirectional"))
      (node (ref "R29") (pin "1") (pinfunction "1_1") (pintype "passive"))
    )
    (net (code "59") (name "LCD_D0") (class "Default")
      (node (ref "CON1") (pin "67") (pinfunction "PE0_67") (pintype "passive"))
      (node (ref "CON2") (pin "A4") (pinfunction "D0_A4") (pintype "bidirectional"))
    )
    (net (code "60") (name "LCD_D1") (class "Default")
      (node (ref "CON1") (pin "68") (pinfunction "PE1_68") (pintype "passive"))
      (node (ref "CON2") (pin "B5") (pinfunction "D1_B5") (pintype "bidirectional"))
    )
    (net (code "61") (name "LCD_D2") (class "Default")
      (node (ref "CON1") (pin "65") (pinfunction "PE2_65") (pintype "passive"))
      (node (ref "CON2") (pin "A5") (pinfunction "D2_A5") (pintype "bidirectional"))
    )
    (net (code "62") (name "LCD_D3") (class "Default")
      (node (ref "CON1") (pin "66") (pinfunction "PE3_66") (pintype "passive"))
      (node (ref "CON2") (pin "B6") (pinfunction "D3_B6") (pintype "bidirectional"))
    )
    (net (code "63") (name "LCD_D4") (class "Default")
      (node (ref "CON1") (pin "63") (pinfunction "PE4_63") (pintype "passive"))
      (node (ref "CON2") (pin "A6") (pinfunction "D4_A6") (pintype "bidirectional"))
    )
    (net (code "64") (name "LCD_D5") (class "Default")
      (node (ref "CON1") (pin "64") (pinfunction "PE5_64") (pintype "passive"))
      (node (ref "CON2") (pin "B7") (pinfunction "D5_B7") (pintype "bidirectional"))
    )
    (net (code "65") (name "LCD_D6") (class "Default")
      (node (ref "CON1") (pin "61") (pinfunction "PE6_61") (pintype "passive"))
      (node (ref "CON2") (pin "A7") (pinfunction "D6_A7") (pintype "bidirectional"))
    )
    (net (code "66") (name "LCD_D7") (class "Default")
      (node (ref "CON1") (pin "25") (pinfunction "PE7_25") (pintype "passive"))
      (node (ref "CON2") (pin "B8") (pinfunction "D7_B8") (pintype "bidirectional"))
    )
    (net (code "67") (name "LCD_D8") (class "Default")
      (node (ref "CON1") (pin "26") (pinfunction "PE8_26") (pintype "passive"))
      (node (ref "CON2") (pin "A8") (pinfunction "D8_A8") (pintype "bidirectional"))
    )
    (net (code "68") (name "LCD_D9") (class "Default")
      (node (ref "CON1") (pin "27") (pinfunction "PE9_27") (pintype "passive"))
      (node (ref "CON2") (pin "B9") (pinfunction "D9_B9") (pintype "bidirectional"))
    )
    (net (code "69") (name "LCD_D10") (class "Default")
      (node (ref "CON1") (pin "28") (pinfunction "PE10_28") (pintype "passive"))
      (node (ref "CON2") (pin "A9") (pinfunction "D10_A9") (pintype "bidirectional"))
    )
    (net (code "70") (name "LCD_D11") (class "Default")
      (node (ref "CON1") (pin "29") (pinfunction "PE11_29") (pintype "passive"))
      (node (ref "CON2") (pin "B10") (pinfunction "D11_B10") (pintype "bidirectional"))
    )
    (net (code "71") (name "LCD_D12") (class "Default")
      (node (ref "CON1") (pin "30") (pinfunction "PE12_30") (pintype "passive"))
      (node (ref "CON2") (pin "A10") (pinfunction "D12_A10") (pintype "bidirectional"))
    )
    (net (code "72") (name "LCD_D13") (class "Default")
      (node (ref "CON1") (pin "31") (pinfunction "PE13_31") (pintype "passive"))
      (node (ref "CON2") (pin "B11") (pinfunction "D13_B11") (pintype "bidirectional"))
    )
    (net (code "73") (name "LCD_D14") (class "Default")
      (node (ref "CON1") (pin "32") (pinfunction "PE14_32") (pintype "passive"))
      (node (ref "CON2") (pin "A11") (pinfunction "D14_A11") (pintype "bidirectional"))
    )
    (net (code "74") (name "LCD_D15") (class "Default")
      (node (ref "CON1") (pin "33") (pinfunction "PE15_33") (pintype "passive"))
      (node (ref "CON2") (pin "B12") (pinfunction "D15_B12") (pintype "bidirectional"))
    )
    (net (code "75") (name "LCD_RE") (class "Default")
      (node (ref "CON1") (pin "36") (pinfunction "PB12_36") (pintype "passive"))
      (node (ref "CON2") (pin "A2") (pinfunction "RE_A2") (pintype "bidirectional"))
      (node (ref "R30") (pin "2") (pinfunction "2_2") (pintype "passive"))
    )
    (net (code "76") (name "LCD_RES") (class "Default")
      (node (ref "CON1") (pin "35") (pinfunction "PB11_35") (pintype "passive"))
      (node (ref "CON2") (pin "B2") (pinfunction "RES_B2") (pintype "bidirectional"))
    )
    (net (code "77") (name "LCD_RS") (class "Default")
      (node (ref "CON1") (pin "38") (pinfunction "PB14_38") (pintype "passive"))
      (node (ref "CON2") (pin "A3") (pinfunction "RS_A3") (pintype "bidirectional"))
    )
    (net (code "78") (name "LCD_TE") (class "Default")
      (node (ref "CON1") (pin "40") (pinfunction "PD8_40") (pintype "passive"))
      (node (ref "CON2") (pin "A12") (pinfunction "TE_A12") (pintype "output"))
    )
    (net (code "79") (name "LCD_WE") (class "Default")
      (node (ref "CON1") (pin "37") (pinfunction "PB13_37") (pintype "passive"))
      (node (ref "CON2") (pin "B3") (pinfunction "WE_B3") (pintype "bidirectional"))
    )
    (net (code "80") (name "N$23") (class "Default")
      (node (ref "CON1") (pin "7") (pinfunction "PC1_7") (pintype "passive"))
    )
    (net (code "81") (name "Net-(D1-A)") (class "Default")
      (node (ref "D1") (pin "1") (pinfunction "A_1") (pintype "passive"))
      (node (ref "L3") (pin "2") (pinfunction "2_2") (pintype "passive"))
      (node (ref "U3") (pin "1") (pinfunction "SW_1") (pintype "bidirectional"))
    )
    (net (code "82") (name "Net-(IC1A-O)") (class "Default")
      (node (ref "IC1") (pin "2") (pinfunction "O_2") (pintype "output"))
      (node (ref "R24") (pin "1") (pinfunction "1_1") (pintype "passive"))
    )
    (net (code "83") (name "Net-(IC1B-I)") (class "Default")
      (node (ref "IC1") (pin "3") (pinfunction "I_3") (pintype "input"))
      (node (ref "R23") (pin "1") (pinfunction "1_1") (pintype "passive"))
    )
    (net (code "84") (name "Net-(R15-Pad1)") (class "Default")
      (node (ref "R15") (pin "1") (pinfunction "1_1") (pintype "passive"))
      (node (ref "R20") (pin "1") (pinfunction "1_1") (pintype "passive"))
    )
    (net (code "85") (name "Net-(R21-Pad1)") (class "Default")
      (node (ref "R21") (pin "1") (pinfunction "1_1") (pintype "passive"))
      (node (ref "R27") (pin "2") (pinfunction "2_2") (pintype "passive"))
      (node (ref "U$1") (pin "3") (pinfunction "3_3") (pintype "bidirectional"))
    )
    (net (code "86") (name "Net-(R22-Pad1)") (class "Default")
      (node (ref "R22") (pin "1") (pinfunction "1_1") (pintype "passive"))
      (node (ref "R28") (pin "2") (pinfunction "2_2") (pintype "passive"))
      (node (ref "U$2") (pin "3") (pinfunction "3_3") (pintype "bidirectional"))
    )
    (net (code "87") (name "Net-(R23-Pad2)") (class "Default")
      (node (ref "R23") (pin "2") (pinfunction "2_2") (pintype "passive"))
      (node (ref "U$1") (pin "4") (pinfunction "4_4") (pintype "bidirectional"))
    )
    (net (code "88") (name "Net-(R24-Pad2)") (class "Default")
      (node (ref "R24") (pin "2") (pinfunction "2_2") (pintype "passive"))
      (node (ref "U$2") (pin "4") (pinfunction "4_4") (pintype "bidirectional"))
    )
    (net (code "89") (name "Net-(R25-Pad2)") (class "Default")
      (node (ref "R25") (pin "2") (pinfunction "2_2") (pintype "passive"))
      (node (ref "U$1") (pin "5") (pinfunction "5_5") (pintype "bidirectional"))
    )
    (net (code "90") (name "Net-(R26-Pad2)") (class "Default")
      (node (ref "R26") (pin "2") (pinfunction "2_2") (pintype "passive"))
      (node (ref "U$2") (pin "5") (pinfunction "5_5") (pintype "bidirectional"))
    )
    (net (code "91") (name "Net-(SV2-Pad3)") (class "Default")
      (node (ref "SV2") (pin "3") (pinfunction "3_3") (pintype "passive"))
      (node (ref "SV3") (pin "1") (pinfunction "1_1") (pintype "passive"))
    )
    (net (code "92") (name "Net-(U1-ADJ)") (class "Default")
      (node (ref "C1") (pin "1") (pinfunction "1_1") (pintype "passive"))
      (node (ref "R2") (pin "2") (pinfunction "2_2") (pintype "passive"))
      (node (ref "R3") (pin "2") (pinfunction "2_2") (pintype "passive"))
      (node (ref "U1") (pin "4") (pinfunction "ADJ_4") (pintype "bidirectional"))
    )
    (net (code "93") (name "Net-(U3-EN)") (class "Default")
      (node (ref "SV4") (pin "2") (pinfunction "2_2") (pintype "passive"))
      (node (ref "U3") (pin "4") (pinfunction "EN_4") (pintype "bidirectional"))
    )
    (net (code "94") (name "Net-(U4-FB)") (class "Default")
      (node (ref "C8") (pin "2") (pinfunction "2_2") (pintype "passive"))
      (node (ref "R7") (pin "2") (pinfunction "2_2") (pintype "passive"))
      (node (ref "R8") (pin "1") (pinfunction "1_1") (pintype "passive"))
      (node (ref "U4") (pin "4") (pinfunction "FB_4") (pintype "bidirectional"))
    )
    (net (code "95") (name "Net-(U4-SW)") (class "Default")
      (node (ref "L1") (pin "1") (pinfunction "1_1") (pintype "passive"))
      (node (ref "U4") (pin "5") (pinfunction "SW_5") (pintype "bidirectional"))
    )
    (net (code "96") (name "Net-(U6-ADJ)") (class "Default")
      (node (ref "C4") (pin "1") (pinfunction "1_1") (pintype "passive"))
      (node (ref "R5") (pin "2") (pinfunction "2_2") (pintype "passive"))
      (node (ref "R6") (pin "2") (pinfunction "2_2") (pintype "passive"))
      (node (ref "U6") (pin "4") (pinfunction "ADJ_4") (pintype "bidirectional"))
    )
    (net (code "97") (name "Net-(U7-FB)") (class "Default")
      (node (ref "C11") (pin "2") (pinfunction "2_2") (pintype "passive"))
      (node (ref "R10") (pin "2") (pinfunction "2_2") (pintype "passive"))
      (node (ref "R9") (pin "1") (pinfunction "1_1") (pintype "passive"))
      (node (ref "U7") (pin "4") (pinfunction "FB_4") (pintype "bidirectional"))
    )
    (net (code "98") (name "Net-(U7-SW)") (class "Default")
      (node (ref "L2") (pin "1") (pinfunction "1_1") (pintype "passive"))
      (node (ref "U7") (pin "5") (pinfunction "SW_5") (pintype "bidirectional"))
    )
    (net (code "99") (name "Net-(U8-ADJ)") (class "Default")
      (node (ref "C15") (pin "1") (pinfunction "1_1") (pintype "passive"))
      (node (ref "R15") (pin "2") (pinfunction "2_2") (pintype "passive"))
      (node (ref "R16") (pin "2") (pinfunction "2_2") (pintype "passive"))
      (node (ref "U8") (pin "4") (pinfunction "ADJ_4") (pintype "bidirectional"))
    )
    (net (code "100") (name "Net-(U9-INT)") (class "Default")
      (node (ref "R33") (pin "1") (pinfunction "1_1") (pintype "passive"))
      (node (ref "U9") (pin "8") (pinfunction "INT_8") (pintype "output"))
    )
    (net (code "101") (name "Net-(U9-SCL)") (class "Default")
      (node (ref "R31") (pin "1") (pinfunction "1_1") (pintype "passive"))
      (node (ref "R35") (pin "2") (pinfunction "2_2") (pintype "passive"))
      (node (ref "U9") (pin "44") (pinfunction "SCL_44") (pintype "input"))
    )
    (net (code "102") (name "Net-(U9-SDA)") (class "Default")
      (node (ref "R32") (pin "1") (pinfunction "1_1") (pintype "passive"))
      (node (ref "R36") (pin "2") (pinfunction "2_2") (pintype "passive"))
      (node (ref "U9") (pin "1") (pinfunction "SDA_1") (pintype "bidirectional"))
    )
    (net (code "103") (name "Net-(U9-VCAP)") (class "Default")
      (node (ref "C13") (pin "1") (pinfunction "1_1") (pintype "passive"))
      (node (ref "U9") (pin "7") (pinfunction "VCAP_7") (pintype "power_in"))
    )
    (net (code "104") (name "Net-(U9-VDD)") (class "Default")
      (node (ref "C28") (pin "1") (pinfunction "1_1") (pintype "passive"))
      (node (ref "R19") (pin "2") (pinfunction "2_2") (pintype "passive"))
      (node (ref "U9") (pin "40") (pinfunction "VDD_40") (pintype "power_in"))
    )
    (net (code "105") (name "Net-(U9-VDD_2)") (class "Default")
      (node (ref "C30") (pin "1") (pinfunction "1_1") (pintype "passive"))
      (node (ref "R17") (pin "2") (pinfunction "2_2") (pintype "passive"))
      (node (ref "U9") (pin "17") (pinfunction "VDD_2_17") (pintype "power_in"))
    )
    (net (code "106") (name "Net-(U9-VDD_3)") (class "Default")
      (node (ref "C29") (pin "1") (pinfunction "1_1") (pintype "passive"))
      (node (ref "R18") (pin "2") (pinfunction "2_2") (pintype "passive"))
      (node (ref "U9") (pin "28") (pinfunction "VDD_3_28") (pintype "power_in"))
    )
    (net (code "107") (name "Net-(U9-~{RESET})") (class "Default")
      (node (ref "R34") (pin "1") (pinfunction "1_1") (pintype "passive"))
      (node (ref "R37") (pin "2") (pinfunction "2_2") (pintype "passive"))
      (node (ref "U9") (pin "18") (pinfunction "~{RESET}_18") (pintype "input"))
    )
    (net (code "108") (name "Net-(U10-FB)") (class "Default")
      (node (ref "R51") (pin "2") (pinfunction "2_2") (pintype "passive"))
      (node (ref "R52") (pin "1") (pinfunction "1_1") (pintype "passive"))
      (node (ref "U10") (pin "10") (pinfunction "FB_10") (pintype "input"))
    )
    (net (code "109") (name "Net-(U10-L1)") (class "Default")
      (node (ref "L4") (pin "2") (pinfunction "2_2") (pintype "passive"))
      (node (ref "U10") (pin "4") (pinfunction "L1_4") (pintype "input"))
    )
    (net (code "110") (name "Net-(U10-L2)") (class "Default")
      (node (ref "L4") (pin "1") (pinfunction "1_1") (pintype "passive"))
      (node (ref "U10") (pin "2") (pinfunction "L2_2") (pintype "input"))
    )
    (net (code "111") (name "Net-(U11-5WSX-)") (class "Default")
      (node (ref "C34") (pin "1") (pinfunction "1_1") (pintype "passive"))
      (node (ref "R43") (pin "1") (pinfunction "1_1") (pintype "passive"))
      (node (ref "U11") (pin "17") (pinfunction "5WSX-_17") (pintype "bidirectional"))
      (node (ref "X1") (pin "2") (pinfunction "B_2") (pintype "passive"))
    )
    (net (code "112") (name "Net-(U11-M1)") (class "Default")
      (node (ref "SJ2") (pin "2") (pinfunction "2_2") (pintype "passive"))
      (node (ref "U11") (pin "2") (pinfunction "M1_2") (pintype "bidirectional"))
    )
    (net (code "113") (name "Net-(U11-M2)") (class "Default")
      (node (ref "SJ1") (pin "2") (pinfunction "2_2") (pintype "passive"))
      (node (ref "U11") (pin "4") (pinfunction "M2_4") (pintype "bidirectional"))
    )
    (net (code "114") (name "Net-(U11-SCK{slash}SCL{slash}TX)") (class "Default")
      (node (ref "R45") (pin "1") (pinfunction "1_1") (pintype "passive"))
      (node (ref "R50") (pin "2") (pinfunction "2_2") (pintype "passive"))
      (node (ref "U11") (pin "11") (pinfunction "SCK/SCL/TX_11") (pintype "bidirectional"))
    )
    (net (code "115") (name "Net-(U11-SDI{slash}SDA{slash}RX)") (class "Default")
      (node (ref "R44") (pin "1") (pinfunction "1_1") (pintype "passive"))
      (node (ref "R49") (pin "2") (pinfunction "2_2") (pintype "passive"))
      (node (ref "U11") (pin "13") (pinfunction "SDI/SDA/RX_13") (pintype "bidirectional"))
    )
    (net (code "116") (name "Net-(U11-SDO)") (class "Default")
      (node (ref "R46") (pin "1") (pinfunction "1_1") (pintype "passive"))
      (node (ref "U11") (pin "9") (pinfunction "SDO_9") (pintype "bidirectional"))
    )
    (net (code "117") (name "Net-(U11-SQI)") (class "Default")
      (node (ref "R48") (pin "1") (pinfunction "1_1") (pintype "passive"))
      (node (ref "U11") (pin "6") (pinfunction "SQI_6") (pintype "bidirectional"))
    )
    (net (code "118") (name "Net-(U11-SS)") (class "Default")
      (node (ref "R47") (pin "1") (pinfunction "1_1") (pintype "passive"))
      (node (ref "U11") (pin "8") (pinfunction "SS_8") (pintype "bidirectional"))
    )
    (net (code "119") (name "Net-(U11-SX+)") (class "Default")
      (node (ref "R42") (pin "1") (pinfunction "1_1") (pintype "passive"))
      (node (ref "U11") (pin "14") (pinfunction "SX+_14") (pintype "bidirectional"))
      (node (ref "X1") (pin "8") (pinfunction "B_8") (pintype "passive"))
    )
    (net (code "120") (name "Net-(U11-SY+)") (class "Default")
      (node (ref "R41") (pin "1") (pinfunction "1_1") (pintype "passive"))
      (node (ref "U11") (pin "7") (pinfunction "SY+_7") (pintype "bidirectional"))
      (node (ref "X1") (pin "6") (pinfunction "B_6") (pintype "passive"))
    )
    (net (code "121") (name "Net-(U11-SY-)") (class "Default")
      (node (ref "R40") (pin "1") (pinfunction "1_1") (pintype "passive"))
      (node (ref "U11") (pin "3") (pinfunction "SY-_3") (pintype "bidirectional"))
      (node (ref "X1") (pin "4") (pinfunction "B_4") (pintype "passive"))
    )
    (net (code "122") (name "Net-(U11-VDD)") (class "Default")
      (node (ref "C31") (pin "1") (pinfunction "1_1") (pintype "passive"))
      (node (ref "R38") (pin "2") (pinfunction "2_2") (pintype "passive"))
      (node (ref "U11") (pin "1") (pinfunction "VDD_1") (pintype "bidirectional"))
    )
    (net (code "123") (name "Net-(U11-WAKE)") (class "Default")
      (node (ref "R39") (pin "2") (pinfunction "2_2") (pintype "passive"))
      (node (ref "U11") (pin "5") (pinfunction "WAKE_5") (pintype "bidirectional"))
    )
    (net (code "124") (name "Net-(U11-X+)") (class "Default")
      (node (ref "U11") (pin "18") (pinfunction "X+_18") (pintype "bidirectional"))
      (node (ref "X1") (pin "3") (pinfunction "B_3") (pintype "passive"))
    )
    (net (code "125") (name "Net-(U11-X-)") (class "Default")
      (node (ref "C32") (pin "1") (pinfunction "1_1") (pintype "passive"))
      (node (ref "R39") (pin "1") (pinfunction "1_1") (pintype "passive"))
      (node (ref "U11") (pin "19") (pinfunction "X-_19") (pintype "bidirectional"))
      (node (ref "X1") (pin "1") (pinfunction "B_1") (pintype "passive"))
    )
    (net (code "126") (name "Net-(U11-Y+)") (class "Default")
      (node (ref "U11") (pin "15") (pinfunction "Y+_15") (pintype "bidirectional"))
      (node (ref "X1") (pin "7") (pinfunction "B_7") (pintype "passive"))
    )
    (net (code "127") (name "Net-(U11-Y-)") (class "Default")
      (node (ref "C33") (pin "1") (pinfunction "1_1") (pintype "passive"))
      (node (ref "U11") (pin "16") (pinfunction "Y-_16") (pintype "bidirectional"))
      (node (ref "X1") (pin "5") (pinfunction "B_5") (pintype "passive"))
    )
    (net (code "128") (name "SCL") (class "Default")
      (node (ref "R31") (pin "2") (pinfunction "2_2") (pintype "passive"))
      (node (ref "R45") (pin "2") (pinfunction "2_2") (pintype "passive"))
    )
    (net (code "129") (name "SDA") (class "Default")
      (node (ref "R32") (pin "2") (pinfunction "2_2") (pintype "passive"))
      (node (ref "R44") (pin "2") (pinfunction "2_2") (pintype "passive"))
    )
    (net (code "130") (name "STACKMAT_RXD") (class "Default")
      (node (ref "CON1") (pin "14") (pinfunction "PA2_14") (pintype "passive"))
      (node (ref "IC1") (pin "4") (pinfunction "O_4") (pintype "output"))
    )
    (net (code "131") (name "STACKMAT_SENSE") (class "Default")
      (node (ref "CON1") (pin "20") (pinfunction "PC4_20") (pintype "passive"))
      (node (ref "R25") (pin "1") (pinfunction "1_1") (pintype "passive"))
    )
    (net (code "132") (name "STACKMAT_VERSION") (class "Default")
      (node (ref "CON1") (pin "10") (pinfunction "PC2_10") (pintype "passive"))
      (node (ref "R27") (pin "1") (pinfunction "1_1") (pintype "passive"))
    )
    (net (code "133") (name "TOUCH_C_INT") (class "Default")
      (node (ref "R34") (pin "2") (pinfunction "2_2") (pintype "passive"))
    )
    (net (code "134") (name "TOUCH_C_RESET") (class "Default")
      (node (ref "R33") (pin "2") (pinfunction "2_2") (pintype "passive"))
    )
    (net (code "135") (name "TOUCH_R_INT1") (class "Default")
      (node (ref "R46") (pin "2") (pinfunction "2_2") (pintype "passive"))
    )
    (net (code "136") (name "TOUCH_R_INT2") (class "Default")
      (node (ref "R48") (pin "2") (pinfunction "2_2") (pintype "passive"))
    )
    (net (code "137") (name "TOUCH_R_SS") (class "Default")
      (node (ref "R47") (pin "2") (pinfunction "2_2") (pintype "passive"))
    )
    (net (code "138") (name "V") (class "Default")
      (node (ref "C10") (pin "1") (pinfunction "1_1") (pintype "passive"))
      (node (ref "C12") (pin "1") (pinfunction "1_1") (pintype "passive"))
      (node (ref "C17") (pin "2") (pinfunction "2_2") (pintype "passive"))
      (node (ref "C3") (pin "2") (pinfunction "2_2") (pintype "passive"))
      (node (ref "C35") (pin "1") (pinfunction "1_1") (pintype "passive"))
      (node (ref "C36") (pin "1") (pinfunction "1_1") (pintype "passive"))
      (node (ref "C6") (pin "2") (pinfunction "2_2") (pintype "passive"))
      (node (ref "C7") (pin "1") (pinfunction "1_1") (pintype "passive"))
      (node (ref "L3") (pin "1") (pinfunction "1_1") (pintype "passive"))
      (node (ref "SV2") (pin "2") (pinfunction "2_2") (pintype "passive"))
      (node (ref "SV2") (pin "4") (pinfunction "4_4") (pintype "passive"))
      (node (ref "SV2") (pin "6") (pinfunction "6_6") (pintype "passive"))
      (node (ref "SV2") (pin "8") (pinfunction "8_8") (pintype "passive"))
      (node (ref "SV4") (pin "1") (pinfunction "1_1") (pintype "passive"))
      (node (ref "U1") (pin "1") (pinfunction "VIN_1") (pintype "bidirectional"))
      (node (ref "U10") (pin "5") (pinfunction "VIN_5") (pintype "input"))
      (node (ref "U10") (pin "6") (pinfunction "EN_6") (pintype "input"))
      (node (ref "U10") (pin "7") (pinfunction "PS/SYNC_7") (pintype "input"))
      (node (ref "U10") (pin "8") (pinfunction "VINA_8") (pintype "input"))
      (node (ref "U3") (pin "5") (pinfunction "VIN_5") (pintype "bidirectional"))
      (node (ref "U4") (pin "1") (pinfunction "VIN_1") (pintype "bidirectional"))
      (node (ref "U6") (pin "1") (pinfunction "VIN_1") (pintype "bidirectional"))
      (node (ref "U7") (pin "1") (pinfunction "VIN_1") (pintype "bidirectional"))
      (node (ref "U8") (pin "1") (pinfunction "VIN_1") (pintype "bidirectional"))
    )
    (net (code "139") (name "V_LCD_N") (class "Default")
      (node (ref "C26") (pin "1") (pinfunction "1_1") (pintype "passive"))
      (node (ref "CON2") (pin "A16") (pinfunction "LCD_BL_K_A16") (pintype "bidirectional"))
      (node (ref "R11") (pin "1") (pinfunction "1_1") (pintype "passive"))
      (node (ref "U3") (pin "3") (pinfunction "VFB_3") (pintype "bidirectional"))
    )
    (net (code "140") (name "V_LCD_P") (class "Default")
      (node (ref "C14") (pin "1") (pinfunction "1_1") (pintype "passive"))
      (node (ref "C25") (pin "1") (pinfunction "1_1") (pintype "passive"))
      (node (ref "CON2") (pin "B16") (pinfunction "LCD_BL_A_B16") (pintype "bidirectional"))
      (node (ref "D1") (pin "3") (pinfunction "C_3") (pintype "passive"))
    )
    (net (code "141") (name "unconnected-(CON1A-NC-Pad48)") (class "Default")
      (node (ref "CON1") (pin "48") (pinfunction "NC_48") (pintype "passive"))
    )
    (net (code "142") (name "unconnected-(CON1A-NRST-Pad6)") (class "Default")
      (node (ref "CON1") (pin "6") (pinfunction "NRST_6") (pintype "passive"))
    )
    (net (code "143") (name "unconnected-(CON1A-PA0-Pad12)") (class "Default")
      (node (ref "CON1") (pin "12") (pinfunction "PA0_12") (pintype "passive"))
    )
    (net (code "144") (name "unconnected-(CON1A-PA4-Pad16)") (class "Default")
      (node (ref "CON1") (pin "16") (pinfunction "PA4_16") (pintype "passive"))
    )
    (net (code "145") (name "unconnected-(CON1A-PA5-Pad15)") (class "Default")
      (node (ref "CON1") (pin "15") (pinfunction "PA5_15") (pintype "passive"))
    )
    (net (code "146") (name "unconnected-(CON1A-PA6-Pad18)") (class "Default")
      (node (ref "CON1") (pin "18") (pinfunction "PA6_18") (pintype "passive"))
    )
    (net (code "147") (name "unconnected-(CON1A-PA7-Pad17)") (class "Default")
      (node (ref "CON1") (pin "17") (pinfunction "PA7_17") (pintype "passive"))
    )
    (net (code "148") (name "unconnected-(CON1A-PB0-Pad22)") (class "Default")
      (node (ref "CON1") (pin "22") (pinfunction "PB0_22") (pintype "passive"))
    )
    (net (code "149") (name "unconnected-(CON1A-PB1-Pad21)") (class "Default")
      (node (ref "CON1") (pin "21") (pinfunction "PB1_21") (pintype "passive"))
    )
    (net (code "150") (name "unconnected-(CON1A-PB2-Pad24)") (class "Default")
      (node (ref "CON1") (pin "24") (pinfunction "PB2_24") (pintype "passive"))
    )
    (net (code "151") (name "unconnected-(CON1A-PB9-Pad41)") (class "Default")
      (node (ref "CON1") (pin "41") (pinfunction "PB9_41") (pintype "passive"))
    )
    (net (code "152") (name "unconnected-(CON1A-PB10-Pad34)") (class "Default")
      (node (ref "CON1") (pin "34") (pinfunction "PB10_34") (pintype "passive"))
    )
    (net (code "153") (name "unconnected-(CON1A-PC0-Pad8)") (class "Default")
      (node (ref "CON1") (pin "8") (pinfunction "PC0_8") (pintype "passive"))
    )
    (net (code "154") (name "unconnected-(CON1A-PC3-Pad9)") (class "Default")
      (node (ref "CON1") (pin "9") (pinfunction "PC3_9") (pintype "passive"))
    )
    (net (code "155") (name "unconnected-(CON1A-PD10-Pad42)") (class "Default")
      (node (ref "CON1") (pin "42") (pinfunction "PD10_42") (pintype "passive"))
    )
    (net (code "156") (name "unconnected-(CON1A-PD11-Pad43)") (class "Default")
      (node (ref "CON1") (pin "43") (pinfunction "PD11_43") (pintype "passive"))
    )
    (net (code "157") (name "unconnected-(CON1A-PD12-Pad44)") (class "Default")
      (node (ref "CON1") (pin "44") (pinfunction "PD12_44") (pintype "passive"))
    )
    (net (code "158") (name "unconnected-(CON1A-PD13-Pad45)") (class "Default")
      (node (ref "CON1") (pin "45") (pinfunction "PD13_45") (pintype "passive"))
    )
    (net (code "159") (name "unconnected-(CON1A-PD14-Pad46)") (class "Default")
      (node (ref "CON1") (pin "46") (pinfunction "PD14_46") (pintype "passive"))
    )
    (net (code "160") (name "unconnected-(CON1A-PD15-Pad47)") (class "Default")
      (node (ref "CON1") (pin "47") (pinfunction "PD15_47") (pintype "passive"))
    )
    (net (code "161") (name "unconnected-(CON1A-VDD-Pad3)") (class "Default")
      (node (ref "CON1") (pin "3") (pinfunction "VDD_3") (pintype "passive"))
    )
    (net (code "162") (name "unconnected-(CON1A-VDD-Pad4)") (class "Default")
      (node (ref "CON1") (pin "4") (pinfunction "VDD_4") (pintype "passive"))
    )
    (net (code "163") (name "unconnected-(CON1B-BOOT0-Pad71)") (class "Default")
      (node (ref "CON1") (pin "71") (pinfunction "BOOT0_71") (pintype "passive"))
    )
    (net (code "164") (name "unconnected-(CON1B-PA8-Pad93)") (class "Default")
      (node (ref "CON1") (pin "93") (pinfunction "PA8_93") (pintype "passive"))
    )
    (net (code "165") (name "unconnected-(CON1B-PA9-Pad94)") (class "Default")
      (node (ref "CON1") (pin "94") (pinfunction "PA9_94") (pintype "passive"))
    )
    (net (code "166") (name "unconnected-(CON1B-PA10-Pad91)") (class "Default")
      (node (ref "CON1") (pin "91") (pinfunction "PA10_91") (pintype "passive"))
    )
    (net (code "167") (name "unconnected-(CON1B-PA13-Pad92)") (class "Default")
      (node (ref "CON1") (pin "92") (pinfunction "PA13_92") (pintype "passive"))
    )
    (net (code "168") (name "unconnected-(CON1B-PA14-Pad89)") (class "Default")
      (node (ref "CON1") (pin "89") (pinfunction "PA14_89") (pintype "passive"))
    )
    (net (code "169") (name "unconnected-(CON1B-PA15-Pad90)") (class "Default")
      (node (ref "CON1") (pin "90") (pinfunction "PA15_90") (pintype "passive"))
    )
    (net (code "170") (name "unconnected-(CON1B-PB3-Pad78)") (class "Default")
      (node (ref "CON1") (pin "78") (pinfunction "PB3_78") (pintype "passive"))
    )
    (net (code "171") (name "unconnected-(CON1B-PB4-Pad75)") (class "Default")
      (node (ref "CON1") (pin "75") (pinfunction "PB4_75") (pintype "passive"))
    )
    (net (code "172") (name "unconnected-(CON1B-PB5-Pad76)") (class "Default")
      (node (ref "CON1") (pin "76") (pinfunction "PB5_76") (pintype "passive"))
    )
    (net (code "173") (name "unconnected-(CON1B-PB6-Pad73)") (class "Default")
      (node (ref "CON1") (pin "73") (pinfunction "PB6_73") (pintype "passive"))
    )
    (net (code "174") (name "unconnected-(CON1B-PB7-Pad74)") (class "Default")
      (node (ref "CON1") (pin "74") (pinfunction "PB7_74") (pintype "passive"))
    )
    (net (code "175") (name "unconnected-(CON1B-PB8-Pad69)") (class "Default")
      (node (ref "CON1") (pin "69") (pinfunction "PB8_69") (pintype "passive"))
    )
    (net (code "176") (name "unconnected-(CON1B-PB9-Pad70)") (class "Default")
      (node (ref "CON1") (pin "70") (pinfunction "PB9_70") (pintype "passive"))
    )
    (net (code "177") (name "unconnected-(CON1B-PC6-Pad97)") (class "Default")
      (node (ref "CON1") (pin "97") (pinfunction "PC6_97") (pintype "passive"))
    )
    (net (code "178") (name "unconnected-(CON1B-PC7-Pad98)") (class "Default")
      (node (ref "CON1") (pin "98") (pinfunction "PC7_98") (pintype "passive"))
    )
    (net (code "179") (name "unconnected-(CON1B-PC8-Pad95)") (class "Default")
      (node (ref "CON1") (pin "95") (pinfunction "PC8_95") (pintype "passive"))
    )
    (net (code "180") (name "unconnected-(CON1B-PC9-Pad96)") (class "Default")
      (node (ref "CON1") (pin "96") (pinfunction "PC9_96") (pintype "passive"))
    )
    (net (code "181") (name "unconnected-(CON1B-PC10-Pad87)") (class "Default")
      (node (ref "CON1") (pin "87") (pinfunction "PC10_87") (pintype "passive"))
    )
    (net (code "182") (name "unconnected-(CON1B-PC11-Pad88)") (class "Default")
      (node (ref "CON1") (pin "88") (pinfunction "PC11_88") (pintype "passive"))
    )
    (net (code "183") (name "unconnected-(CON1B-PC12-Pad85)") (class "Default")
      (node (ref "CON1") (pin "85") (pinfunction "PC12_85") (pintype "passive"))
    )
    (net (code "184") (name "unconnected-(CON1B-PC13-Pad62)") (class "Default")
      (node (ref "CON1") (pin "62") (pinfunction "PC13_62") (pintype "passive"))
    )
    (net (code "185") (name "unconnected-(CON1B-PC14-Pad59)") (class "Default")
      (node (ref "CON1") (pin "59") (pinfunction "PC14_59") (pintype "passive"))
    )
    (net (code "186") (name "unconnected-(CON1B-PC15-Pad60)") (class "Default")
      (node (ref "CON1") (pin "60") (pinfunction "PC15_60") (pintype "passive"))
    )
    (net (code "187") (name "unconnected-(CON1B-PD0-Pad86)") (class "Default")
      (node (ref "CON1") (pin "86") (pinfunction "PD0_86") (pintype "passive"))
    )
    (net (code "188") (name "unconnected-(CON1B-PD1-Pad83)") (class "Default")
      (node (ref "CON1") (pin "83") (pinfunction "PD1_83") (pintype "passive"))
    )
    (net (code "189") (name "unconnected-(CON1B-PD2-Pad84)") (class "Default")
      (node (ref "CON1") (pin "84") (pinfunction "PD2_84") (pintype "passive"))
    )
    (net (code "190") (name "unconnected-(CON1B-PD3-Pad81)") (class "Default")
      (node (ref "CON1") (pin "81") (pinfunction "PD3_81") (pintype "passive"))
    )
    (net (code "191") (name "unconnected-(CON1B-PD4-Pad82)") (class "Default")
      (node (ref "CON1") (pin "82") (pinfunction "PD4_82") (pintype "passive"))
    )
    (net (code "192") (name "unconnected-(CON1B-PD5-Pad79)") (class "Default")
      (node (ref "CON1") (pin "79") (pinfunction "PD5_79") (pintype "passive"))
    )
    (net (code "193") (name "unconnected-(CON1B-PD6-Pad80)") (class "Default")
      (node (ref "CON1") (pin "80") (pinfunction "PD6_80") (pintype "passive"))
    )
    (net (code "194") (name "unconnected-(CON1B-PD7-Pad77)") (class "Default")
      (node (ref "CON1") (pin "77") (pinfunction "PD7_77") (pintype "passive"))
    )
    (net (code "195") (name "unconnected-(CON1B-PH0-Pad57)") (class "Default")
      (node (ref "CON1") (pin "57") (pinfunction "PH0_57") (pintype "passive"))
    )
    (net (code "196") (name "unconnected-(CON1B-PH1-Pad58)") (class "Default")
      (node (ref "CON1") (pin "58") (pinfunction "PH1_58") (pintype "passive"))
    )
    (net (code "197") (name "unconnected-(CON1B-VDD-Pad72)") (class "Default")
      (node (ref "CON1") (pin "72") (pinfunction "VDD_72") (pintype "passive"))
    )
    (net (code "198") (name "unconnected-(SV3-Pad2)") (class "Default")
      (node (ref "SV3") (pin "2") (pinfunction "2_2") (pintype "passive"))
    )
    (net (code "199") (name "unconnected-(U2-GND-PadP$10)") (class "Default")
      (node (ref "U2") (pin "P$10") (pinfunction "GND_P$10") (pintype "bidirectional"))
    )
    (net (code "200") (name "unconnected-(U2-I{slash}O_1_H-Pad19)") (class "Default")
      (node (ref "U2") (pin "19") (pinfunction "I/O_1_H_19") (pintype "bidirectional"))
    )
    (net (code "201") (name "unconnected-(U2-I{slash}O_1_L-Pad2)") (class "Default")
      (node (ref "U2") (pin "2") (pinfunction "I/O_1_L_2") (pintype "bidirectional"))
    )
    (net (code "202") (name "unconnected-(U2-I{slash}O_2_H-Pad3)") (class "Default")
      (node (ref "U2") (pin "3") (pinfunction "I/O_2_H_3") (pintype "bidirectional"))
    )
    (net (code "203") (name "unconnected-(U2-I{slash}O_2_L-Pad18)") (class "Default")
      (node (ref "U2") (pin "18") (pinfunction "I/O_2_L_18") (pintype "bidirectional"))
    )
    (net (code "204") (name "unconnected-(U2-I{slash}O_3_H-Pad17)") (class "Default")
      (node (ref "U2") (pin "17") (pinfunction "I/O_3_H_17") (pintype "bidirectional"))
    )
    (net (code "205") (name "unconnected-(U2-I{slash}O_3_L-Pad4)") (class "Default")
      (node (ref "U2") (pin "4") (pinfunction "I/O_3_L_4") (pintype "bidirectional"))
    )
    (net (code "206") (name "unconnected-(U2-I{slash}O_4_H-Pad5)") (class "Default")
      (node (ref "U2") (pin "5") (pinfunction "I/O_4_H_5") (pintype "bidirectional"))
    )
    (net (code "207") (name "unconnected-(U2-I{slash}O_4_L-Pad16)") (class "Default")
      (node (ref "U2") (pin "16") (pinfunction "I/O_4_L_16") (pintype "bidirectional"))
    )
    (net (code "208") (name "unconnected-(U2-I{slash}O_5_H-Pad15)") (class "Default")
      (node (ref "U2") (pin "15") (pinfunction "I/O_5_H_15") (pintype "bidirectional"))
    )
    (net (code "209") (name "unconnected-(U2-I{slash}O_5_L-Pad6)") (class "Default")
      (node (ref "U2") (pin "6") (pinfunction "I/O_5_L_6") (pintype "bidirectional"))
    )
    (net (code "210") (name "unconnected-(U2-I{slash}O_6_H-Pad7)") (class "Default")
      (node (ref "U2") (pin "7") (pinfunction "I/O_6_H_7") (pintype "bidirectional"))
    )
    (net (code "211") (name "unconnected-(U2-I{slash}O_6_L-Pad14)") (class "Default")
      (node (ref "U2") (pin "14") (pinfunction "I/O_6_L_14") (pintype "bidirectional"))
    )
    (net (code "212") (name "unconnected-(U2-I{slash}O_7_H-Pad13)") (class "Default")
      (node (ref "U2") (pin "13") (pinfunction "I/O_7_H_13") (pintype "bidirectional"))
    )
    (net (code "213") (name "unconnected-(U2-I{slash}O_7_L-Pad8)") (class "Default")
      (node (ref "U2") (pin "8") (pinfunction "I/O_7_L_8") (pintype "bidirectional"))
    )
    (net (code "214") (name "unconnected-(U2-I{slash}O_8_H-PadP$9)") (class "Default")
      (node (ref "U2") (pin "P$9") (pinfunction "I/O_8_H_P$9") (pintype "bidirectional"))
    )
    (net (code "215") (name "unconnected-(U2-I{slash}O_8_L-Pad12)") (class "Default")
      (node (ref "U2") (pin "12") (pinfunction "I/O_8_L_12") (pintype "bidirectional"))
    )
    (net (code "216") (name "unconnected-(U2-OE-Pad11)") (class "Default")
      (node (ref "U2") (pin "11") (pinfunction "OE_11") (pintype "bidirectional"))
    )
    (net (code "217") (name "unconnected-(U2-VCC-Pad20)") (class "Default")
      (node (ref "U2") (pin "20") (pinfunction "VCC_20") (pintype "bidirectional"))
    )
    (net (code "218") (name "unconnected-(U2-VL-Pad1)") (class "Default")
      (node (ref "U2") (pin "1") (pinfunction "VL_1") (pintype "bidirectional"))
    )
    (net (code "219") (name "unconnected-(U5-GND-PadP$10)") (class "Default")
      (node (ref "U5") (pin "P$10") (pinfunction "GND_P$10") (pintype "bidirectional"))
    )
    (net (code "220") (name "unconnected-(U5-I{slash}O_1_H-Pad19)") (class "Default")
      (node (ref "U5") (pin "19") (pinfunction "I/O_1_H_19") (pintype "bidirectional"))
    )
    (net (code "221") (name "unconnected-(U5-I{slash}O_1_L-Pad2)") (class "Default")
      (node (ref "U5") (pin "2") (pinfunction "I/O_1_L_2") (pintype "bidirectional"))
    )
    (net (code "222") (name "unconnected-(U5-I{slash}O_2_H-Pad3)") (class "Default")
      (node (ref "U5") (pin "3") (pinfunction "I/O_2_H_3") (pintype "bidirectional"))
    )
    (net (code "223") (name "unconnected-(U5-I{slash}O_2_L-Pad18)") (class "Default")
      (node (ref "U5") (pin "18") (pinfunction "I/O_2_L_18") (pintype "bidirectional"))
    )
    (net (code "224") (name "unconnected-(U5-I{slash}O_3_H-Pad17)") (class "Default")
      (node (ref "U5") (pin "17") (pinfunction "I/O_3_H_17") (pintype "bidirectional"))
    )
    (net (code "225") (name "unconnected-(U5-I{slash}O_3_L-Pad4)") (class "Default")
      (node (ref "U5") (pin "4") (pinfunction "I/O_3_L_4") (pintype "bidirectional"))
    )
    (net (code "226") (name "unconnected-(U5-I{slash}O_4_H-Pad5)") (class "Default")
      (node (ref "U5") (pin "5") (pinfunction "I/O_4_H_5") (pintype "bidirectional"))
    )
    (net (code "227") (name "unconnected-(U5-I{slash}O_4_L-Pad16)") (class "Default")
      (node (ref "U5") (pin "16") (pinfunction "I/O_4_L_16") (pintype "bidirectional"))
    )
    (net (code "228") (name "unconnected-(U5-I{slash}O_5_H-Pad15)") (class "Default")
      (node (ref "U5") (pin "15") (pinfunction "I/O_5_H_15") (pintype "bidirectional"))
    )
    (net (code "229") (name "unconnected-(U5-I{slash}O_5_L-Pad6)") (class "Default")
      (node (ref "U5") (pin "6") (pinfunction "I/O_5_L_6") (pintype "bidirectional"))
    )
    (net (code "230") (name "unconnected-(U5-I{slash}O_6_H-Pad7)") (class "Default")
      (node (ref "U5") (pin "7") (pinfunction "I/O_6_H_7") (pintype "bidirectional"))
    )
    (net (code "231") (name "unconnected-(U5-I{slash}O_6_L-Pad14)") (class "Default")
      (node (ref "U5") (pin "14") (pinfunction "I/O_6_L_14") (pintype "bidirectional"))
    )
    (net (code "232") (name "unconnected-(U5-I{slash}O_7_H-Pad13)") (class "Default")
      (node (ref "U5") (pin "13") (pinfunction "I/O_7_H_13") (pintype "bidirectional"))
    )
    (net (code "233") (name "unconnected-(U5-I{slash}O_7_L-Pad8)") (class "Default")
      (node (ref "U5") (pin "8") (pinfunction "I/O_7_L_8") (pintype "bidirectional"))
    )
    (net (code "234") (name "unconnected-(U5-I{slash}O_8_H-PadP$9)") (class "Default")
      (node (ref "U5") (pin "P$9") (pinfunction "I/O_8_H_P$9") (pintype "bidirectional"))
    )
    (net (code "235") (name "unconnected-(U5-I{slash}O_8_L-Pad12)") (class "Default")
      (node (ref "U5") (pin "12") (pinfunction "I/O_8_L_12") (pintype "bidirectional"))
    )
    (net (code "236") (name "unconnected-(U5-OE-Pad11)") (class "Default")
      (node (ref "U5") (pin "11") (pinfunction "OE_11") (pintype "bidirectional"))
    )
    (net (code "237") (name "unconnected-(U5-VCC-Pad20)") (class "Default")
      (node (ref "U5") (pin "20") (pinfunction "VCC_20") (pintype "bidirectional"))
    )
    (net (code "238") (name "unconnected-(U5-VL-Pad1)") (class "Default")
      (node (ref "U5") (pin "1") (pinfunction "VL_1") (pintype "bidirectional"))
    )
    (net (code "239") (name "unconnected-(U9-N{slash}C-Pad9)") (class "Default")
      (node (ref "U9") (pin "9") (pinfunction "N/C_9") (pintype "no_connect"))
    )
  )
)
